# Sheet4_Matrix.net
KiCad netlist of a schematic drawn in Altium Designer
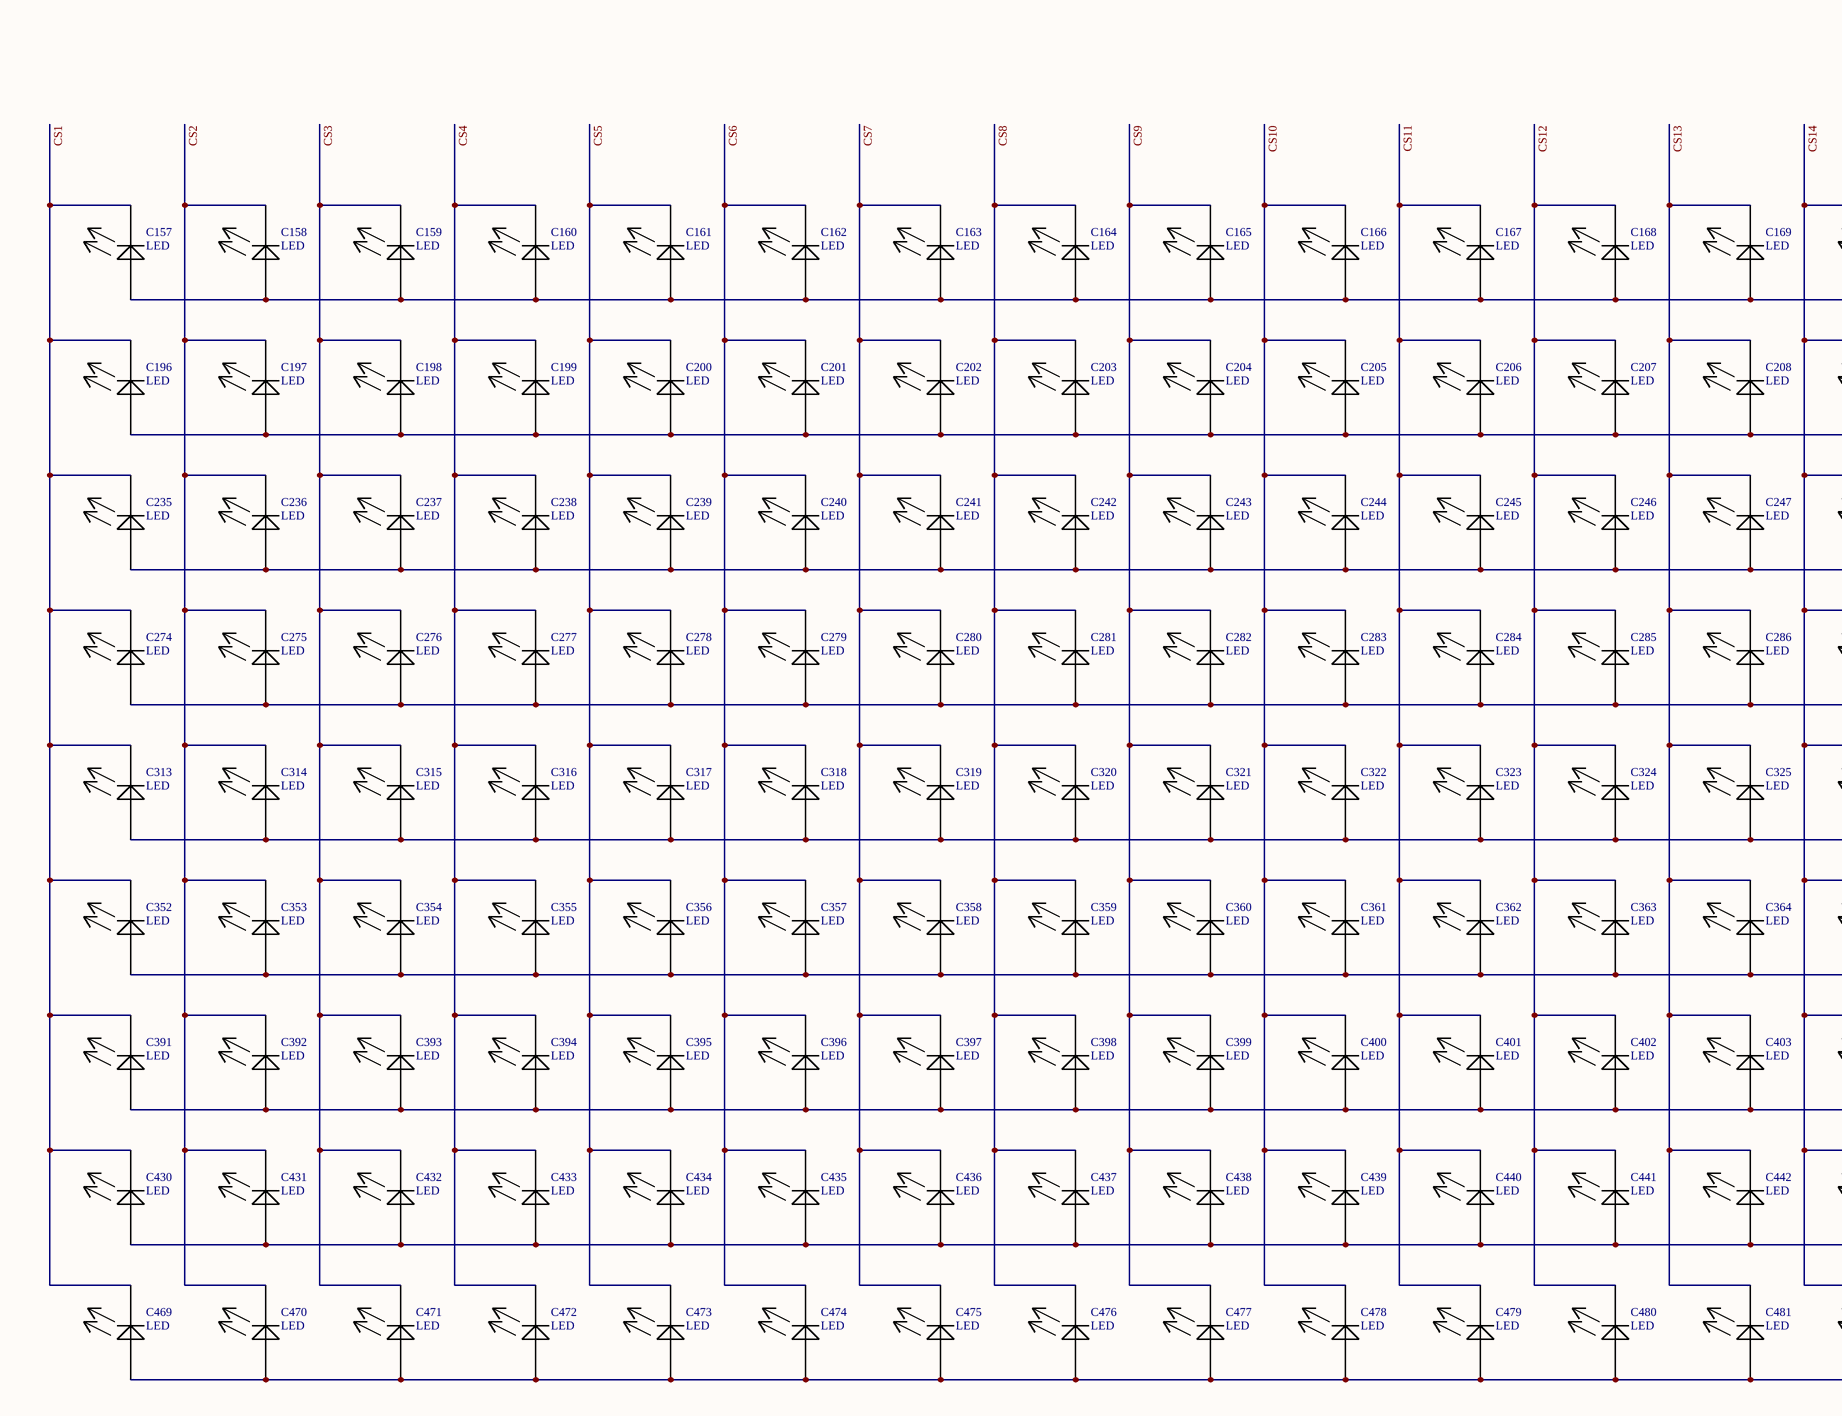
[diagram p0: Sheet4_Matrix.SchDoc, left]
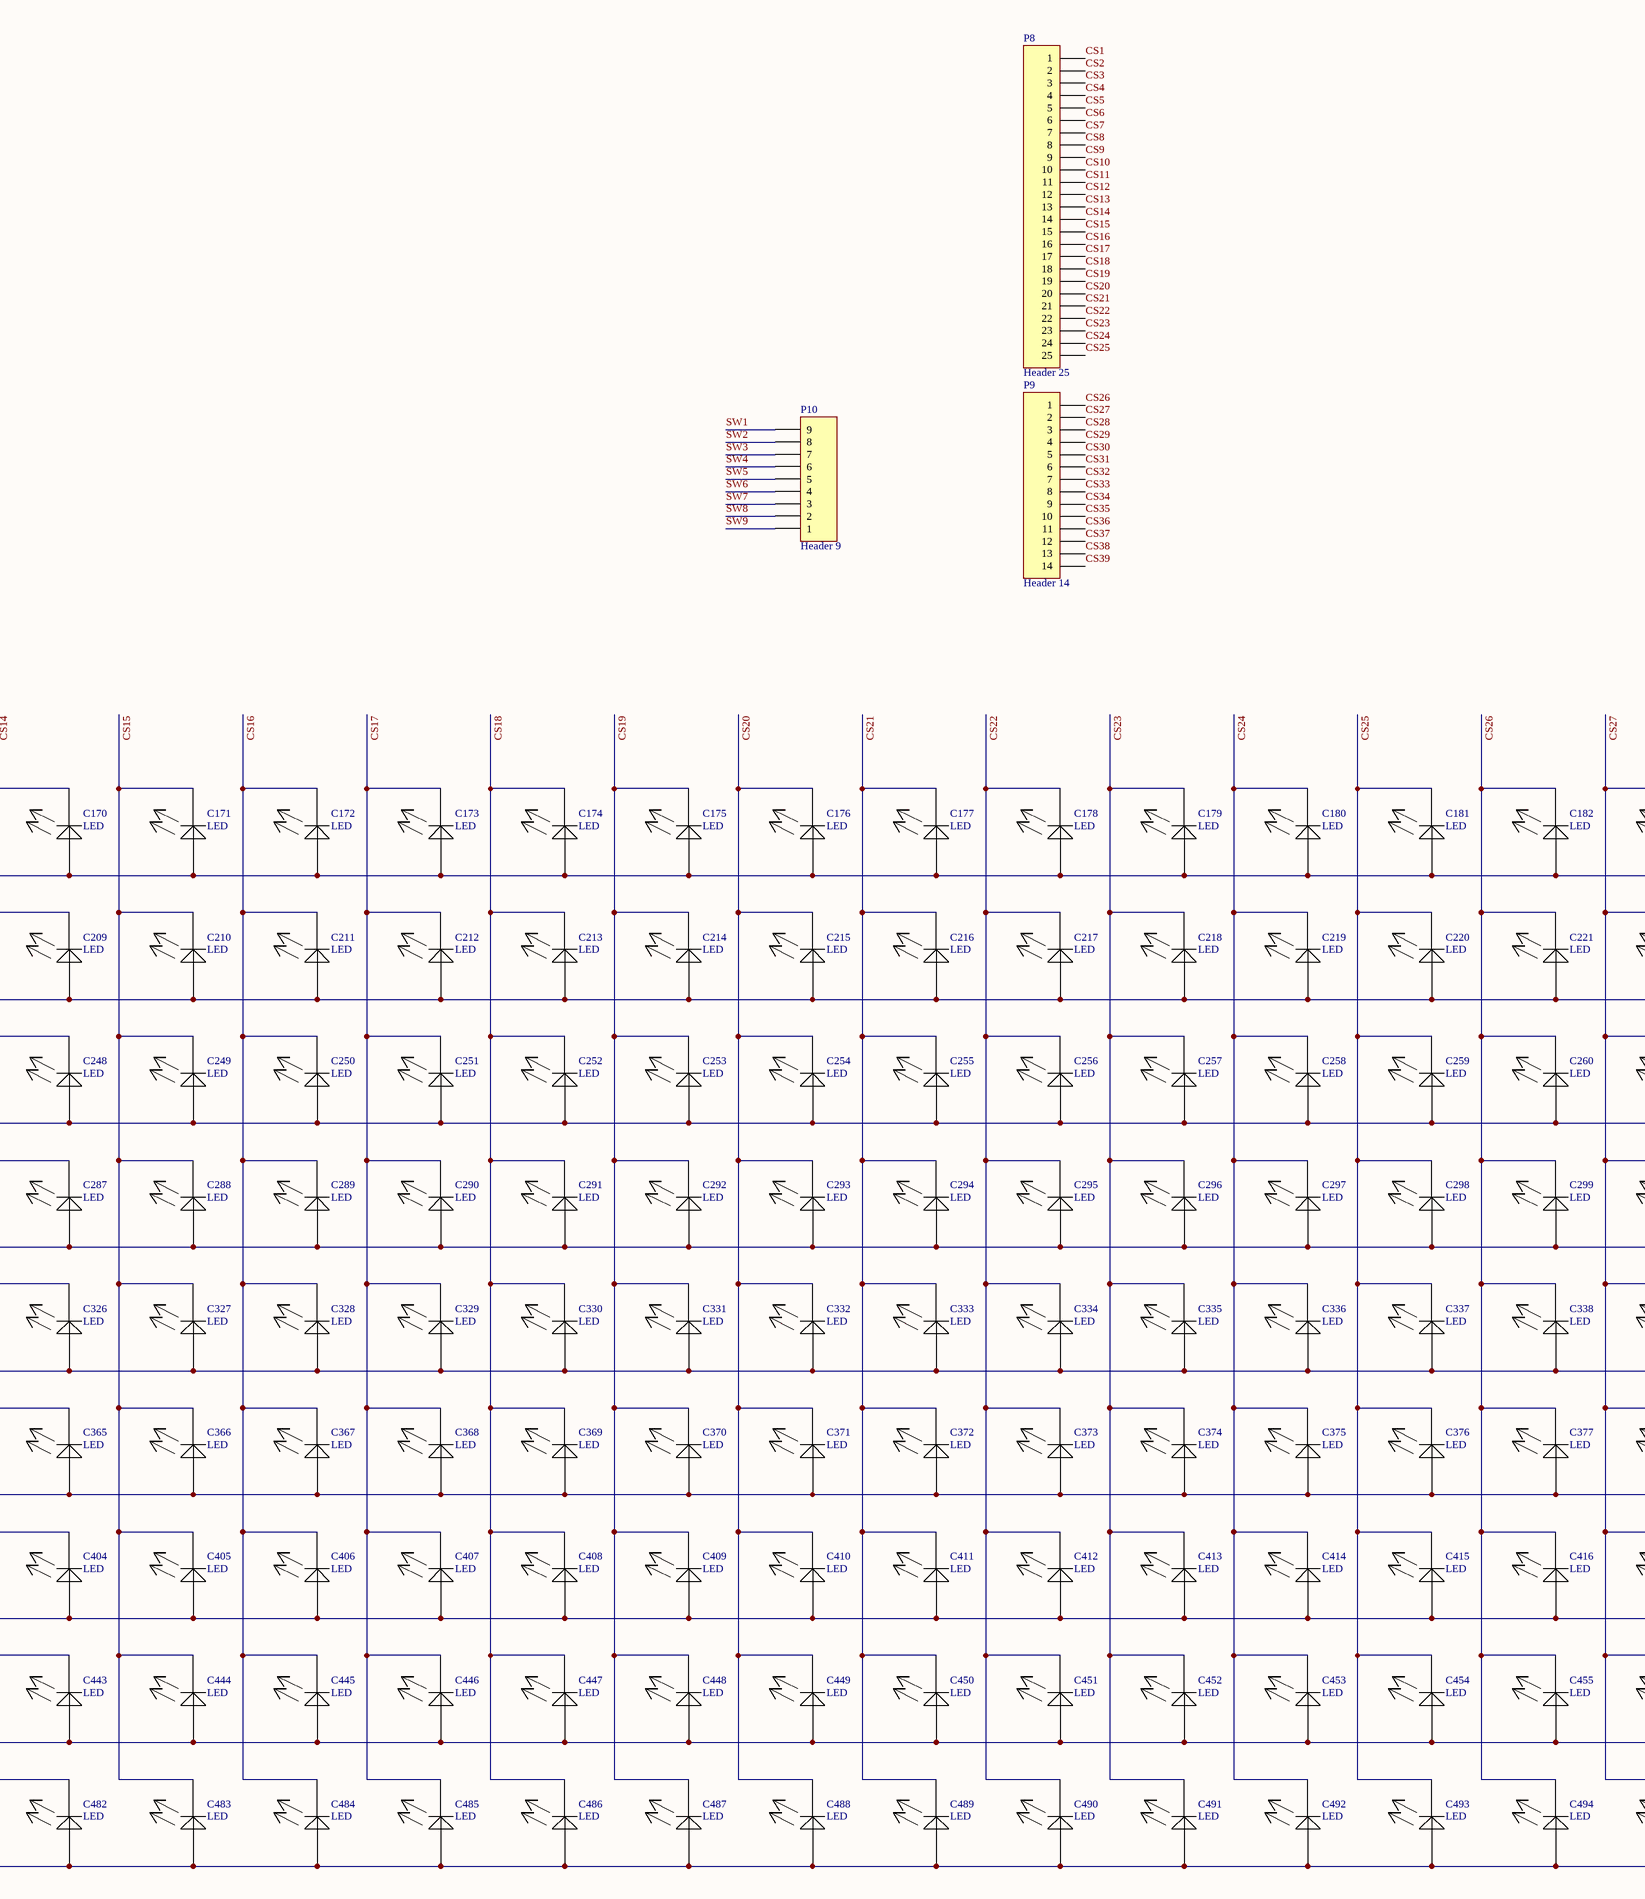
[diagram p1: Sheet4_Matrix.SchDoc, middle]
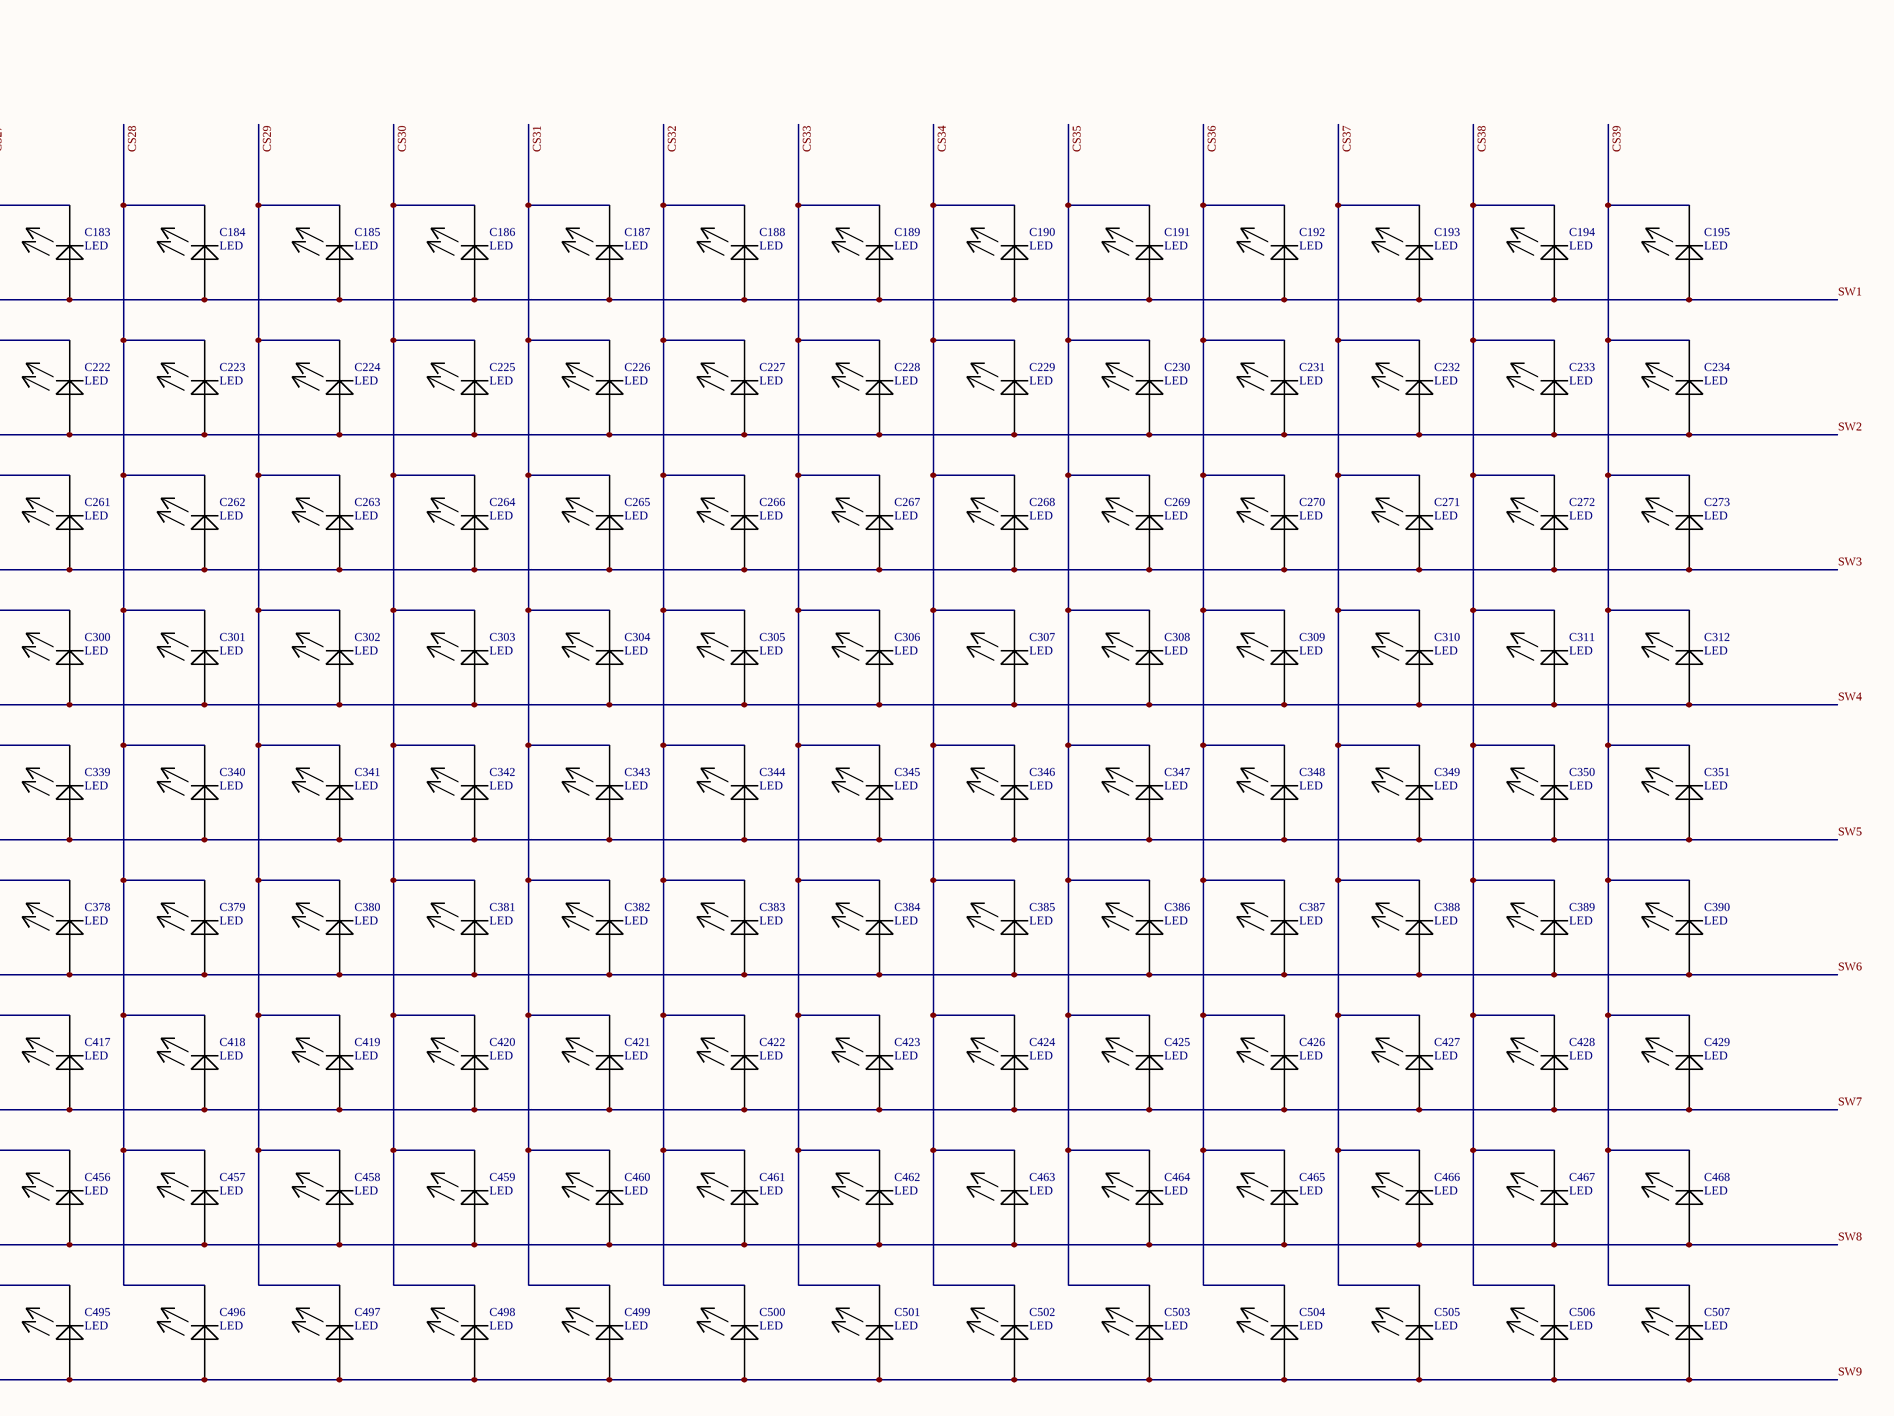
[diagram p2: Sheet4_Matrix.SchDoc, right]

(export (version "E")
  (design (tool "Eeschema 10.0.6"))
  (components
    (comp (ref "C157") (value "LED") (footprint "LED 0603(2)") (libsource (lib "LEDs") (part "LED")))
    (comp (ref "C158") (value "LED") (footprint "LED 0603(2)") (libsource (lib "LEDs") (part "LED")))
    (comp (ref "C159") (value "LED") (footprint "LED 0603(2)") (libsource (lib "LEDs") (part "LED")))
    (comp (ref "C160") (value "LED") (footprint "LED 0603(2)") (libsource (lib "LEDs") (part "LED")))
    (comp (ref "C161") (value "LED") (footprint "LED 0603(2)") (libsource (lib "LEDs") (part "LED")))
    (comp (ref "C162") (value "LED") (footprint "LED 0603(2)") (libsource (lib "LEDs") (part "LED")))
    (comp (ref "C163") (value "LED") (footprint "LED 0603(2)") (libsource (lib "LEDs") (part "LED")))
    (comp (ref "C164") (value "LED") (footprint "LED 0603(2)") (libsource (lib "LEDs") (part "LED")))
    (comp (ref "C165") (value "LED") (footprint "LED 0603(2)") (libsource (lib "LEDs") (part "LED")))
    (comp (ref "C166") (value "LED") (footprint "LED 0603(2)") (libsource (lib "LEDs") (part "LED")))
    (comp (ref "C167") (value "LED") (footprint "LED 0603(2)") (libsource (lib "LEDs") (part "LED")))
    (comp (ref "C168") (value "LED") (footprint "LED 0603(2)") (libsource (lib "LEDs") (part "LED")))
    (comp (ref "C169") (value "LED") (footprint "LED 0603(2)") (libsource (lib "LEDs") (part "LED")))
    (comp (ref "C170") (value "LED") (footprint "LED 0603(2)") (libsource (lib "LEDs") (part "LED")))
    (comp (ref "C171") (value "LED") (footprint "LED 0603(2)") (libsource (lib "LEDs") (part "LED")))
    (comp (ref "C172") (value "LED") (footprint "LED 0603(2)") (libsource (lib "LEDs") (part "LED")))
    (comp (ref "C173") (value "LED") (footprint "LED 0603(2)") (libsource (lib "LEDs") (part "LED")))
    (comp (ref "C174") (value "LED") (footprint "LED 0603(2)") (libsource (lib "LEDs") (part "LED")))
    (comp (ref "C175") (value "LED") (footprint "LED 0603(2)") (libsource (lib "LEDs") (part "LED")))
    (comp (ref "C176") (value "LED") (footprint "LED 0603(2)") (libsource (lib "LEDs") (part "LED")))
    (comp (ref "C177") (value "LED") (footprint "LED 0603(2)") (libsource (lib "LEDs") (part "LED")))
    (comp (ref "C178") (value "LED") (footprint "LED 0603(2)") (libsource (lib "LEDs") (part "LED")))
    (comp (ref "C179") (value "LED") (footprint "LED 0603(2)") (libsource (lib "LEDs") (part "LED")))
    (comp (ref "C180") (value "LED") (footprint "LED 0603(2)") (libsource (lib "LEDs") (part "LED")))
    (comp (ref "C181") (value "LED") (footprint "LED 0603(2)") (libsource (lib "LEDs") (part "LED")))
    (comp (ref "C182") (value "LED") (footprint "LED 0603(2)") (libsource (lib "LEDs") (part "LED")))
    (comp (ref "C183") (value "LED") (footprint "LED 0603(2)") (libsource (lib "LEDs") (part "LED")))
    (comp (ref "C184") (value "LED") (footprint "LED 0603(2)") (libsource (lib "LEDs") (part "LED")))
    (comp (ref "C185") (value "LED") (footprint "LED 0603(2)") (libsource (lib "LEDs") (part "LED")))
    (comp (ref "C186") (value "LED") (footprint "LED 0603(2)") (libsource (lib "LEDs") (part "LED")))
    (comp (ref "C187") (value "LED") (footprint "LED 0603(2)") (libsource (lib "LEDs") (part "LED")))
    (comp (ref "C188") (value "LED") (footprint "LED 0603(2)") (libsource (lib "LEDs") (part "LED")))
    (comp (ref "C189") (value "LED") (footprint "LED 0603(2)") (libsource (lib "LEDs") (part "LED")))
    (comp (ref "C190") (value "LED") (footprint "LED 0603(2)") (libsource (lib "LEDs") (part "LED")))
    (comp (ref "C191") (value "LED") (footprint "LED 0603(2)") (libsource (lib "LEDs") (part "LED")))
    (comp (ref "C192") (value "LED") (footprint "LED 0603(2)") (libsource (lib "LEDs") (part "LED")))
    (comp (ref "C193") (value "LED") (footprint "LED 0603(2)") (libsource (lib "LEDs") (part "LED")))
    (comp (ref "C194") (value "LED") (footprint "LED 0603(2)") (libsource (lib "LEDs") (part "LED")))
    (comp (ref "C195") (value "LED") (footprint "LED 0603(2)") (libsource (lib "LEDs") (part "LED")))
    (comp (ref "C196") (value "LED") (footprint "LED 0603(2)") (libsource (lib "LEDs") (part "LED")))
    (comp (ref "C197") (value "LED") (footprint "LED 0603(2)") (libsource (lib "LEDs") (part "LED")))
    (comp (ref "C198") (value "LED") (footprint "LED 0603(2)") (libsource (lib "LEDs") (part "LED")))
    (comp (ref "C199") (value "LED") (footprint "LED 0603(2)") (libsource (lib "LEDs") (part "LED")))
    (comp (ref "C200") (value "LED") (footprint "LED 0603(2)") (libsource (lib "LEDs") (part "LED")))
    (comp (ref "C201") (value "LED") (footprint "LED 0603(2)") (libsource (lib "LEDs") (part "LED")))
    (comp (ref "C202") (value "LED") (footprint "LED 0603(2)") (libsource (lib "LEDs") (part "LED")))
    (comp (ref "C203") (value "LED") (footprint "LED 0603(2)") (libsource (lib "LEDs") (part "LED")))
    (comp (ref "C204") (value "LED") (footprint "LED 0603(2)") (libsource (lib "LEDs") (part "LED")))
    (comp (ref "C205") (value "LED") (footprint "LED 0603(2)") (libsource (lib "LEDs") (part "LED")))
    (comp (ref "C206") (value "LED") (footprint "LED 0603(2)") (libsource (lib "LEDs") (part "LED")))
    (comp (ref "C207") (value "LED") (footprint "LED 0603(2)") (libsource (lib "LEDs") (part "LED")))
    (comp (ref "C208") (value "LED") (footprint "LED 0603(2)") (libsource (lib "LEDs") (part "LED")))
    (comp (ref "C209") (value "LED") (footprint "LED 0603(2)") (libsource (lib "LEDs") (part "LED")))
    (comp (ref "C210") (value "LED") (footprint "LED 0603(2)") (libsource (lib "LEDs") (part "LED")))
    (comp (ref "C211") (value "LED") (footprint "LED 0603(2)") (libsource (lib "LEDs") (part "LED")))
    (comp (ref "C212") (value "LED") (footprint "LED 0603(2)") (libsource (lib "LEDs") (part "LED")))
    (comp (ref "C213") (value "LED") (footprint "LED 0603(2)") (libsource (lib "LEDs") (part "LED")))
    (comp (ref "C214") (value "LED") (footprint "LED 0603(2)") (libsource (lib "LEDs") (part "LED")))
    (comp (ref "C215") (value "LED") (footprint "LED 0603(2)") (libsource (lib "LEDs") (part "LED")))
    (comp (ref "C216") (value "LED") (footprint "LED 0603(2)") (libsource (lib "LEDs") (part "LED")))
    (comp (ref "C217") (value "LED") (footprint "LED 0603(2)") (libsource (lib "LEDs") (part "LED")))
    (comp (ref "C218") (value "LED") (footprint "LED 0603(2)") (libsource (lib "LEDs") (part "LED")))
    (comp (ref "C219") (value "LED") (footprint "LED 0603(2)") (libsource (lib "LEDs") (part "LED")))
    (comp (ref "C220") (value "LED") (footprint "LED 0603(2)") (libsource (lib "LEDs") (part "LED")))
    (comp (ref "C221") (value "LED") (footprint "LED 0603(2)") (libsource (lib "LEDs") (part "LED")))
    (comp (ref "C222") (value "LED") (footprint "LED 0603(2)") (libsource (lib "LEDs") (part "LED")))
    (comp (ref "C223") (value "LED") (footprint "LED 0603(2)") (libsource (lib "LEDs") (part "LED")))
    (comp (ref "C224") (value "LED") (footprint "LED 0603(2)") (libsource (lib "LEDs") (part "LED")))
    (comp (ref "C225") (value "LED") (footprint "LED 0603(2)") (libsource (lib "LEDs") (part "LED")))
    (comp (ref "C226") (value "LED") (footprint "LED 0603(2)") (libsource (lib "LEDs") (part "LED")))
    (comp (ref "C227") (value "LED") (footprint "LED 0603(2)") (libsource (lib "LEDs") (part "LED")))
    (comp (ref "C228") (value "LED") (footprint "LED 0603(2)") (libsource (lib "LEDs") (part "LED")))
    (comp (ref "C229") (value "LED") (footprint "LED 0603(2)") (libsource (lib "LEDs") (part "LED")))
    (comp (ref "C230") (value "LED") (footprint "LED 0603(2)") (libsource (lib "LEDs") (part "LED")))
    (comp (ref "C231") (value "LED") (footprint "LED 0603(2)") (libsource (lib "LEDs") (part "LED")))
    (comp (ref "C232") (value "LED") (footprint "LED 0603(2)") (libsource (lib "LEDs") (part "LED")))
    (comp (ref "C233") (value "LED") (footprint "LED 0603(2)") (libsource (lib "LEDs") (part "LED")))
    (comp (ref "C234") (value "LED") (footprint "LED 0603(2)") (libsource (lib "LEDs") (part "LED")))
    (comp (ref "C235") (value "LED") (footprint "LED 0603(2)") (libsource (lib "LEDs") (part "LED")))
    (comp (ref "C236") (value "LED") (footprint "LED 0603(2)") (libsource (lib "LEDs") (part "LED")))
    (comp (ref "C237") (value "LED") (footprint "LED 0603(2)") (libsource (lib "LEDs") (part "LED")))
    (comp (ref "C238") (value "LED") (footprint "LED 0603(2)") (libsource (lib "LEDs") (part "LED")))
    (comp (ref "C239") (value "LED") (footprint "LED 0603(2)") (libsource (lib "LEDs") (part "LED")))
    (comp (ref "C240") (value "LED") (footprint "LED 0603(2)") (libsource (lib "LEDs") (part "LED")))
    (comp (ref "C241") (value "LED") (footprint "LED 0603(2)") (libsource (lib "LEDs") (part "LED")))
    (comp (ref "C242") (value "LED") (footprint "LED 0603(2)") (libsource (lib "LEDs") (part "LED")))
    (comp (ref "C243") (value "LED") (footprint "LED 0603(2)") (libsource (lib "LEDs") (part "LED")))
    (comp (ref "C244") (value "LED") (footprint "LED 0603(2)") (libsource (lib "LEDs") (part "LED")))
    (comp (ref "C245") (value "LED") (footprint "LED 0603(2)") (libsource (lib "LEDs") (part "LED")))
    (comp (ref "C246") (value "LED") (footprint "LED 0603(2)") (libsource (lib "LEDs") (part "LED")))
    (comp (ref "C247") (value "LED") (footprint "LED 0603(2)") (libsource (lib "LEDs") (part "LED")))
    (comp (ref "C248") (value "LED") (footprint "LED 0603(2)") (libsource (lib "LEDs") (part "LED")))
    (comp (ref "C249") (value "LED") (footprint "LED 0603(2)") (libsource (lib "LEDs") (part "LED")))
    (comp (ref "C250") (value "LED") (footprint "LED 0603(2)") (libsource (lib "LEDs") (part "LED")))
    (comp (ref "C251") (value "LED") (footprint "LED 0603(2)") (libsource (lib "LEDs") (part "LED")))
    (comp (ref "C252") (value "LED") (footprint "LED 0603(2)") (libsource (lib "LEDs") (part "LED")))
    (comp (ref "C253") (value "LED") (footprint "LED 0603(2)") (libsource (lib "LEDs") (part "LED")))
    (comp (ref "C254") (value "LED") (footprint "LED 0603(2)") (libsource (lib "LEDs") (part "LED")))
    (comp (ref "C255") (value "LED") (footprint "LED 0603(2)") (libsource (lib "LEDs") (part "LED")))
    (comp (ref "C256") (value "LED") (footprint "LED 0603(2)") (libsource (lib "LEDs") (part "LED")))
    (comp (ref "C257") (value "LED") (footprint "LED 0603(2)") (libsource (lib "LEDs") (part "LED")))
    (comp (ref "C258") (value "LED") (footprint "LED 0603(2)") (libsource (lib "LEDs") (part "LED")))
    (comp (ref "C259") (value "LED") (footprint "LED 0603(2)") (libsource (lib "LEDs") (part "LED")))
    (comp (ref "C260") (value "LED") (footprint "LED 0603(2)") (libsource (lib "LEDs") (part "LED")))
    (comp (ref "C261") (value "LED") (footprint "LED 0603(2)") (libsource (lib "LEDs") (part "LED")))
    (comp (ref "C262") (value "LED") (footprint "LED 0603(2)") (libsource (lib "LEDs") (part "LED")))
    (comp (ref "C263") (value "LED") (footprint "LED 0603(2)") (libsource (lib "LEDs") (part "LED")))
    (comp (ref "C264") (value "LED") (footprint "LED 0603(2)") (libsource (lib "LEDs") (part "LED")))
    (comp (ref "C265") (value "LED") (footprint "LED 0603(2)") (libsource (lib "LEDs") (part "LED")))
    (comp (ref "C266") (value "LED") (footprint "LED 0603(2)") (libsource (lib "LEDs") (part "LED")))
    (comp (ref "C267") (value "LED") (footprint "LED 0603(2)") (libsource (lib "LEDs") (part "LED")))
    (comp (ref "C268") (value "LED") (footprint "LED 0603(2)") (libsource (lib "LEDs") (part "LED")))
    (comp (ref "C269") (value "LED") (footprint "LED 0603(2)") (libsource (lib "LEDs") (part "LED")))
    (comp (ref "C270") (value "LED") (footprint "LED 0603(2)") (libsource (lib "LEDs") (part "LED")))
    (comp (ref "C271") (value "LED") (footprint "LED 0603(2)") (libsource (lib "LEDs") (part "LED")))
    (comp (ref "C272") (value "LED") (footprint "LED 0603(2)") (libsource (lib "LEDs") (part "LED")))
    (comp (ref "C273") (value "LED") (footprint "LED 0603(2)") (libsource (lib "LEDs") (part "LED")))
    (comp (ref "C274") (value "LED") (footprint "LED 0603(2)") (libsource (lib "LEDs") (part "LED")))
    (comp (ref "C275") (value "LED") (footprint "LED 0603(2)") (libsource (lib "LEDs") (part "LED")))
    (comp (ref "C276") (value "LED") (footprint "LED 0603(2)") (libsource (lib "LEDs") (part "LED")))
    (comp (ref "C277") (value "LED") (footprint "LED 0603(2)") (libsource (lib "LEDs") (part "LED")))
    (comp (ref "C278") (value "LED") (footprint "LED 0603(2)") (libsource (lib "LEDs") (part "LED")))
    (comp (ref "C279") (value "LED") (footprint "LED 0603(2)") (libsource (lib "LEDs") (part "LED")))
    (comp (ref "C280") (value "LED") (footprint "LED 0603(2)") (libsource (lib "LEDs") (part "LED")))
    (comp (ref "C281") (value "LED") (footprint "LED 0603(2)") (libsource (lib "LEDs") (part "LED")))
    (comp (ref "C282") (value "LED") (footprint "LED 0603(2)") (libsource (lib "LEDs") (part "LED")))
    (comp (ref "C283") (value "LED") (footprint "LED 0603(2)") (libsource (lib "LEDs") (part "LED")))
    (comp (ref "C284") (value "LED") (footprint "LED 0603(2)") (libsource (lib "LEDs") (part "LED")))
    (comp (ref "C285") (value "LED") (footprint "LED 0603(2)") (libsource (lib "LEDs") (part "LED")))
    (comp (ref "C286") (value "LED") (footprint "LED 0603(2)") (libsource (lib "LEDs") (part "LED")))
    (comp (ref "C287") (value "LED") (footprint "LED 0603(2)") (libsource (lib "LEDs") (part "LED")))
    (comp (ref "C288") (value "LED") (footprint "LED 0603(2)") (libsource (lib "LEDs") (part "LED")))
    (comp (ref "C289") (value "LED") (footprint "LED 0603(2)") (libsource (lib "LEDs") (part "LED")))
    (comp (ref "C290") (value "LED") (footprint "LED 0603(2)") (libsource (lib "LEDs") (part "LED")))
    (comp (ref "C291") (value "LED") (footprint "LED 0603(2)") (libsource (lib "LEDs") (part "LED")))
    (comp (ref "C292") (value "LED") (footprint "LED 0603(2)") (libsource (lib "LEDs") (part "LED")))
    (comp (ref "C293") (value "LED") (footprint "LED 0603(2)") (libsource (lib "LEDs") (part "LED")))
    (comp (ref "C294") (value "LED") (footprint "LED 0603(2)") (libsource (lib "LEDs") (part "LED")))
    (comp (ref "C295") (value "LED") (footprint "LED 0603(2)") (libsource (lib "LEDs") (part "LED")))
    (comp (ref "C296") (value "LED") (footprint "LED 0603(2)") (libsource (lib "LEDs") (part "LED")))
    (comp (ref "C297") (value "LED") (footprint "LED 0603(2)") (libsource (lib "LEDs") (part "LED")))
    (comp (ref "C298") (value "LED") (footprint "LED 0603(2)") (libsource (lib "LEDs") (part "LED")))
    (comp (ref "C299") (value "LED") (footprint "LED 0603(2)") (libsource (lib "LEDs") (part "LED")))
    (comp (ref "C300") (value "LED") (footprint "LED 0603(2)") (libsource (lib "LEDs") (part "LED")))
    (comp (ref "C301") (value "LED") (footprint "LED 0603(2)") (libsource (lib "LEDs") (part "LED")))
    (comp (ref "C302") (value "LED") (footprint "LED 0603(2)") (libsource (lib "LEDs") (part "LED")))
    (comp (ref "C303") (value "LED") (footprint "LED 0603(2)") (libsource (lib "LEDs") (part "LED")))
    (comp (ref "C304") (value "LED") (footprint "LED 0603(2)") (libsource (lib "LEDs") (part "LED")))
    (comp (ref "C305") (value "LED") (footprint "LED 0603(2)") (libsource (lib "LEDs") (part "LED")))
    (comp (ref "C306") (value "LED") (footprint "LED 0603(2)") (libsource (lib "LEDs") (part "LED")))
    (comp (ref "C307") (value "LED") (footprint "LED 0603(2)") (libsource (lib "LEDs") (part "LED")))
    (comp (ref "C308") (value "LED") (footprint "LED 0603(2)") (libsource (lib "LEDs") (part "LED")))
    (comp (ref "C309") (value "LED") (footprint "LED 0603(2)") (libsource (lib "LEDs") (part "LED")))
    (comp (ref "C310") (value "LED") (footprint "LED 0603(2)") (libsource (lib "LEDs") (part "LED")))
    (comp (ref "C311") (value "LED") (footprint "LED 0603(2)") (libsource (lib "LEDs") (part "LED")))
    (comp (ref "C312") (value "LED") (footprint "LED 0603(2)") (libsource (lib "LEDs") (part "LED")))
    (comp (ref "C313") (value "LED") (footprint "LED 0603(2)") (libsource (lib "LEDs") (part "LED")))
    (comp (ref "C314") (value "LED") (footprint "LED 0603(2)") (libsource (lib "LEDs") (part "LED")))
    (comp (ref "C315") (value "LED") (footprint "LED 0603(2)") (libsource (lib "LEDs") (part "LED")))
    (comp (ref "C316") (value "LED") (footprint "LED 0603(2)") (libsource (lib "LEDs") (part "LED")))
    (comp (ref "C317") (value "LED") (footprint "LED 0603(2)") (libsource (lib "LEDs") (part "LED")))
    (comp (ref "C318") (value "LED") (footprint "LED 0603(2)") (libsource (lib "LEDs") (part "LED")))
    (comp (ref "C319") (value "LED") (footprint "LED 0603(2)") (libsource (lib "LEDs") (part "LED")))
    (comp (ref "C320") (value "LED") (footprint "LED 0603(2)") (libsource (lib "LEDs") (part "LED")))
    (comp (ref "C321") (value "LED") (footprint "LED 0603(2)") (libsource (lib "LEDs") (part "LED")))
    (comp (ref "C322") (value "LED") (footprint "LED 0603(2)") (libsource (lib "LEDs") (part "LED")))
    (comp (ref "C323") (value "LED") (footprint "LED 0603(2)") (libsource (lib "LEDs") (part "LED")))
    (comp (ref "C324") (value "LED") (footprint "LED 0603(2)") (libsource (lib "LEDs") (part "LED")))
    (comp (ref "C325") (value "LED") (footprint "LED 0603(2)") (libsource (lib "LEDs") (part "LED")))
    (comp (ref "C326") (value "LED") (footprint "LED 0603(2)") (libsource (lib "LEDs") (part "LED")))
    (comp (ref "C327") (value "LED") (footprint "LED 0603(2)") (libsource (lib "LEDs") (part "LED")))
    (comp (ref "C328") (value "LED") (footprint "LED 0603(2)") (libsource (lib "LEDs") (part "LED")))
    (comp (ref "C329") (value "LED") (footprint "LED 0603(2)") (libsource (lib "LEDs") (part "LED")))
    (comp (ref "C330") (value "LED") (footprint "LED 0603(2)") (libsource (lib "LEDs") (part "LED")))
    (comp (ref "C331") (value "LED") (footprint "LED 0603(2)") (libsource (lib "LEDs") (part "LED")))
    (comp (ref "C332") (value "LED") (footprint "LED 0603(2)") (libsource (lib "LEDs") (part "LED")))
    (comp (ref "C333") (value "LED") (footprint "LED 0603(2)") (libsource (lib "LEDs") (part "LED")))
    (comp (ref "C334") (value "LED") (footprint "LED 0603(2)") (libsource (lib "LEDs") (part "LED")))
    (comp (ref "C335") (value "LED") (footprint "LED 0603(2)") (libsource (lib "LEDs") (part "LED")))
    (comp (ref "C336") (value "LED") (footprint "LED 0603(2)") (libsource (lib "LEDs") (part "LED")))
    (comp (ref "C337") (value "LED") (footprint "LED 0603(2)") (libsource (lib "LEDs") (part "LED")))
    (comp (ref "C338") (value "LED") (footprint "LED 0603(2)") (libsource (lib "LEDs") (part "LED")))
    (comp (ref "C339") (value "LED") (footprint "LED 0603(2)") (libsource (lib "LEDs") (part "LED")))
    (comp (ref "C340") (value "LED") (footprint "LED 0603(2)") (libsource (lib "LEDs") (part "LED")))
    (comp (ref "C341") (value "LED") (footprint "LED 0603(2)") (libsource (lib "LEDs") (part "LED")))
    (comp (ref "C342") (value "LED") (footprint "LED 0603(2)") (libsource (lib "LEDs") (part "LED")))
    (comp (ref "C343") (value "LED") (footprint "LED 0603(2)") (libsource (lib "LEDs") (part "LED")))
    (comp (ref "C344") (value "LED") (footprint "LED 0603(2)") (libsource (lib "LEDs") (part "LED")))
    (comp (ref "C345") (value "LED") (footprint "LED 0603(2)") (libsource (lib "LEDs") (part "LED")))
    (comp (ref "C346") (value "LED") (footprint "LED 0603(2)") (libsource (lib "LEDs") (part "LED")))
    (comp (ref "C347") (value "LED") (footprint "LED 0603(2)") (libsource (lib "LEDs") (part "LED")))
    (comp (ref "C348") (value "LED") (footprint "LED 0603(2)") (libsource (lib "LEDs") (part "LED")))
    (comp (ref "C349") (value "LED") (footprint "LED 0603(2)") (libsource (lib "LEDs") (part "LED")))
    (comp (ref "C350") (value "LED") (footprint "LED 0603(2)") (libsource (lib "LEDs") (part "LED")))
    (comp (ref "C351") (value "LED") (footprint "LED 0603(2)") (libsource (lib "LEDs") (part "LED")))
    (comp (ref "C352") (value "LED") (footprint "LED 0603(2)") (libsource (lib "LEDs") (part "LED")))
    (comp (ref "C353") (value "LED") (footprint "LED 0603(2)") (libsource (lib "LEDs") (part "LED")))
    (comp (ref "C354") (value "LED") (footprint "LED 0603(2)") (libsource (lib "LEDs") (part "LED")))
    (comp (ref "C355") (value "LED") (footprint "LED 0603(2)") (libsource (lib "LEDs") (part "LED")))
    (comp (ref "C356") (value "LED") (footprint "LED 0603(2)") (libsource (lib "LEDs") (part "LED")))
    (comp (ref "C357") (value "LED") (footprint "LED 0603(2)") (libsource (lib "LEDs") (part "LED")))
    (comp (ref "C358") (value "LED") (footprint "LED 0603(2)") (libsource (lib "LEDs") (part "LED")))
    (comp (ref "C359") (value "LED") (footprint "LED 0603(2)") (libsource (lib "LEDs") (part "LED")))
    (comp (ref "C360") (value "LED") (footprint "LED 0603(2)") (libsource (lib "LEDs") (part "LED")))
    (comp (ref "C361") (value "LED") (footprint "LED 0603(2)") (libsource (lib "LEDs") (part "LED")))
    (comp (ref "C362") (value "LED") (footprint "LED 0603(2)") (libsource (lib "LEDs") (part "LED")))
    (comp (ref "C363") (value "LED") (footprint "LED 0603(2)") (libsource (lib "LEDs") (part "LED")))
    (comp (ref "C364") (value "LED") (footprint "LED 0603(2)") (libsource (lib "LEDs") (part "LED")))
    (comp (ref "C365") (value "LED") (footprint "LED 0603(2)") (libsource (lib "LEDs") (part "LED")))
    (comp (ref "C366") (value "LED") (footprint "LED 0603(2)") (libsource (lib "LEDs") (part "LED")))
    (comp (ref "C367") (value "LED") (footprint "LED 0603(2)") (libsource (lib "LEDs") (part "LED")))
    (comp (ref "C368") (value "LED") (footprint "LED 0603(2)") (libsource (lib "LEDs") (part "LED")))
    (comp (ref "C369") (value "LED") (footprint "LED 0603(2)") (libsource (lib "LEDs") (part "LED")))
    (comp (ref "C370") (value "LED") (footprint "LED 0603(2)") (libsource (lib "LEDs") (part "LED")))
    (comp (ref "C371") (value "LED") (footprint "LED 0603(2)") (libsource (lib "LEDs") (part "LED")))
    (comp (ref "C372") (value "LED") (footprint "LED 0603(2)") (libsource (lib "LEDs") (part "LED")))
    (comp (ref "C373") (value "LED") (footprint "LED 0603(2)") (libsource (lib "LEDs") (part "LED")))
    (comp (ref "C374") (value "LED") (footprint "LED 0603(2)") (libsource (lib "LEDs") (part "LED")))
    (comp (ref "C375") (value "LED") (footprint "LED 0603(2)") (libsource (lib "LEDs") (part "LED")))
    (comp (ref "C376") (value "LED") (footprint "LED 0603(2)") (libsource (lib "LEDs") (part "LED")))
    (comp (ref "C377") (value "LED") (footprint "LED 0603(2)") (libsource (lib "LEDs") (part "LED")))
    (comp (ref "C378") (value "LED") (footprint "LED 0603(2)") (libsource (lib "LEDs") (part "LED")))
    (comp (ref "C379") (value "LED") (footprint "LED 0603(2)") (libsource (lib "LEDs") (part "LED")))
    (comp (ref "C380") (value "LED") (footprint "LED 0603(2)") (libsource (lib "LEDs") (part "LED")))
    (comp (ref "C381") (value "LED") (footprint "LED 0603(2)") (libsource (lib "LEDs") (part "LED")))
    (comp (ref "C382") (value "LED") (footprint "LED 0603(2)") (libsource (lib "LEDs") (part "LED")))
    (comp (ref "C383") (value "LED") (footprint "LED 0603(2)") (libsource (lib "LEDs") (part "LED")))
    (comp (ref "C384") (value "LED") (footprint "LED 0603(2)") (libsource (lib "LEDs") (part "LED")))
    (comp (ref "C385") (value "LED") (footprint "LED 0603(2)") (libsource (lib "LEDs") (part "LED")))
    (comp (ref "C386") (value "LED") (footprint "LED 0603(2)") (libsource (lib "LEDs") (part "LED")))
    (comp (ref "C387") (value "LED") (footprint "LED 0603(2)") (libsource (lib "LEDs") (part "LED")))
    (comp (ref "C388") (value "LED") (footprint "LED 0603(2)") (libsource (lib "LEDs") (part "LED")))
    (comp (ref "C389") (value "LED") (footprint "LED 0603(2)") (libsource (lib "LEDs") (part "LED")))
    (comp (ref "C390") (value "LED") (footprint "LED 0603(2)") (libsource (lib "LEDs") (part "LED")))
    (comp (ref "C391") (value "LED") (footprint "LED 0603(2)") (libsource (lib "LEDs") (part "LED")))
    (comp (ref "C392") (value "LED") (footprint "LED 0603(2)") (libsource (lib "LEDs") (part "LED")))
    (comp (ref "C393") (value "LED") (footprint "LED 0603(2)") (libsource (lib "LEDs") (part "LED")))
    (comp (ref "C394") (value "LED") (footprint "LED 0603(2)") (libsource (lib "LEDs") (part "LED")))
    (comp (ref "C395") (value "LED") (footprint "LED 0603(2)") (libsource (lib "LEDs") (part "LED")))
    (comp (ref "C396") (value "LED") (footprint "LED 0603(2)") (libsource (lib "LEDs") (part "LED")))
    (comp (ref "C397") (value "LED") (footprint "LED 0603(2)") (libsource (lib "LEDs") (part "LED")))
    (comp (ref "C398") (value "LED") (footprint "LED 0603(2)") (libsource (lib "LEDs") (part "LED")))
    (comp (ref "C399") (value "LED") (footprint "LED 0603(2)") (libsource (lib "LEDs") (part "LED")))
    (comp (ref "C400") (value "LED") (footprint "LED 0603(2)") (libsource (lib "LEDs") (part "LED")))
    (comp (ref "C401") (value "LED") (footprint "LED 0603(2)") (libsource (lib "LEDs") (part "LED")))
    (comp (ref "C402") (value "LED") (footprint "LED 0603(2)") (libsource (lib "LEDs") (part "LED")))
    (comp (ref "C403") (value "LED") (footprint "LED 0603(2)") (libsource (lib "LEDs") (part "LED")))
    (comp (ref "C404") (value "LED") (footprint "LED 0603(2)") (libsource (lib "LEDs") (part "LED")))
    (comp (ref "C405") (value "LED") (footprint "LED 0603(2)") (libsource (lib "LEDs") (part "LED")))
    (comp (ref "C406") (value "LED") (footprint "LED 0603(2)") (libsource (lib "LEDs") (part "LED")))
    (comp (ref "C407") (value "LED") (footprint "LED 0603(2)") (libsource (lib "LEDs") (part "LED")))
    (comp (ref "C408") (value "LED") (footprint "LED 0603(2)") (libsource (lib "LEDs") (part "LED")))
    (comp (ref "C409") (value "LED") (footprint "LED 0603(2)") (libsource (lib "LEDs") (part "LED")))
    (comp (ref "C410") (value "LED") (footprint "LED 0603(2)") (libsource (lib "LEDs") (part "LED")))
    (comp (ref "C411") (value "LED") (footprint "LED 0603(2)") (libsource (lib "LEDs") (part "LED")))
    (comp (ref "C412") (value "LED") (footprint "LED 0603(2)") (libsource (lib "LEDs") (part "LED")))
    (comp (ref "C413") (value "LED") (footprint "LED 0603(2)") (libsource (lib "LEDs") (part "LED")))
    (comp (ref "C414") (value "LED") (footprint "LED 0603(2)") (libsource (lib "LEDs") (part "LED")))
    (comp (ref "C415") (value "LED") (footprint "LED 0603(2)") (libsource (lib "LEDs") (part "LED")))
    (comp (ref "C416") (value "LED") (footprint "LED 0603(2)") (libsource (lib "LEDs") (part "LED")))
    (comp (ref "C417") (value "LED") (footprint "LED 0603(2)") (libsource (lib "LEDs") (part "LED")))
    (comp (ref "C418") (value "LED") (footprint "LED 0603(2)") (libsource (lib "LEDs") (part "LED")))
    (comp (ref "C419") (value "LED") (footprint "LED 0603(2)") (libsource (lib "LEDs") (part "LED")))
    (comp (ref "C420") (value "LED") (footprint "LED 0603(2)") (libsource (lib "LEDs") (part "LED")))
    (comp (ref "C421") (value "LED") (footprint "LED 0603(2)") (libsource (lib "LEDs") (part "LED")))
    (comp (ref "C422") (value "LED") (footprint "LED 0603(2)") (libsource (lib "LEDs") (part "LED")))
    (comp (ref "C423") (value "LED") (footprint "LED 0603(2)") (libsource (lib "LEDs") (part "LED")))
    (comp (ref "C424") (value "LED") (footprint "LED 0603(2)") (libsource (lib "LEDs") (part "LED")))
    (comp (ref "C425") (value "LED") (footprint "LED 0603(2)") (libsource (lib "LEDs") (part "LED")))
    (comp (ref "C426") (value "LED") (footprint "LED 0603(2)") (libsource (lib "LEDs") (part "LED")))
    (comp (ref "C427") (value "LED") (footprint "LED 0603(2)") (libsource (lib "LEDs") (part "LED")))
    (comp (ref "C428") (value "LED") (footprint "LED 0603(2)") (libsource (lib "LEDs") (part "LED")))
    (comp (ref "C429") (value "LED") (footprint "LED 0603(2)") (libsource (lib "LEDs") (part "LED")))
    (comp (ref "C430") (value "LED") (footprint "LED 0603(2)") (libsource (lib "LEDs") (part "LED")))
    (comp (ref "C431") (value "LED") (footprint "LED 0603(2)") (libsource (lib "LEDs") (part "LED")))
    (comp (ref "C432") (value "LED") (footprint "LED 0603(2)") (libsource (lib "LEDs") (part "LED")))
    (comp (ref "C433") (value "LED") (footprint "LED 0603(2)") (libsource (lib "LEDs") (part "LED")))
    (comp (ref "C434") (value "LED") (footprint "LED 0603(2)") (libsource (lib "LEDs") (part "LED")))
    (comp (ref "C435") (value "LED") (footprint "LED 0603(2)") (libsource (lib "LEDs") (part "LED")))
    (comp (ref "C436") (value "LED") (footprint "LED 0603(2)") (libsource (lib "LEDs") (part "LED")))
    (comp (ref "C437") (value "LED") (footprint "LED 0603(2)") (libsource (lib "LEDs") (part "LED")))
    (comp (ref "C438") (value "LED") (footprint "LED 0603(2)") (libsource (lib "LEDs") (part "LED")))
    (comp (ref "C439") (value "LED") (footprint "LED 0603(2)") (libsource (lib "LEDs") (part "LED")))
    (comp (ref "C440") (value "LED") (footprint "LED 0603(2)") (libsource (lib "LEDs") (part "LED")))
    (comp (ref "C441") (value "LED") (footprint "LED 0603(2)") (libsource (lib "LEDs") (part "LED")))
    (comp (ref "C442") (value "LED") (footprint "LED 0603(2)") (libsource (lib "LEDs") (part "LED")))
    (comp (ref "C443") (value "LED") (footprint "LED 0603(2)") (libsource (lib "LEDs") (part "LED")))
    (comp (ref "C444") (value "LED") (footprint "LED 0603(2)") (libsource (lib "LEDs") (part "LED")))
    (comp (ref "C445") (value "LED") (footprint "LED 0603(2)") (libsource (lib "LEDs") (part "LED")))
    (comp (ref "C446") (value "LED") (footprint "LED 0603(2)") (libsource (lib "LEDs") (part "LED")))
    (comp (ref "C447") (value "LED") (footprint "LED 0603(2)") (libsource (lib "LEDs") (part "LED")))
    (comp (ref "C448") (value "LED") (footprint "LED 0603(2)") (libsource (lib "LEDs") (part "LED")))
    (comp (ref "C449") (value "LED") (footprint "LED 0603(2)") (libsource (lib "LEDs") (part "LED")))
    (comp (ref "C450") (value "LED") (footprint "LED 0603(2)") (libsource (lib "LEDs") (part "LED")))
    (comp (ref "C451") (value "LED") (footprint "LED 0603(2)") (libsource (lib "LEDs") (part "LED")))
    (comp (ref "C452") (value "LED") (footprint "LED 0603(2)") (libsource (lib "LEDs") (part "LED")))
    (comp (ref "C453") (value "LED") (footprint "LED 0603(2)") (libsource (lib "LEDs") (part "LED")))
    (comp (ref "C454") (value "LED") (footprint "LED 0603(2)") (libsource (lib "LEDs") (part "LED")))
    (comp (ref "C455") (value "LED") (footprint "LED 0603(2)") (libsource (lib "LEDs") (part "LED")))
    (comp (ref "C456") (value "LED") (footprint "LED 0603(2)") (libsource (lib "LEDs") (part "LED")))
    (comp (ref "C457") (value "LED") (footprint "LED 0603(2)") (libsource (lib "LEDs") (part "LED")))
    (comp (ref "C458") (value "LED") (footprint "LED 0603(2)") (libsource (lib "LEDs") (part "LED")))
    (comp (ref "C459") (value "LED") (footprint "LED 0603(2)") (libsource (lib "LEDs") (part "LED")))
    (comp (ref "C460") (value "LED") (footprint "LED 0603(2)") (libsource (lib "LEDs") (part "LED")))
    (comp (ref "C461") (value "LED") (footprint "LED 0603(2)") (libsource (lib "LEDs") (part "LED")))
    (comp (ref "C462") (value "LED") (footprint "LED 0603(2)") (libsource (lib "LEDs") (part "LED")))
    (comp (ref "C463") (value "LED") (footprint "LED 0603(2)") (libsource (lib "LEDs") (part "LED")))
    (comp (ref "C464") (value "LED") (footprint "LED 0603(2)") (libsource (lib "LEDs") (part "LED")))
    (comp (ref "C465") (value "LED") (footprint "LED 0603(2)") (libsource (lib "LEDs") (part "LED")))
    (comp (ref "C466") (value "LED") (footprint "LED 0603(2)") (libsource (lib "LEDs") (part "LED")))
    (comp (ref "C467") (value "LED") (footprint "LED 0603(2)") (libsource (lib "LEDs") (part "LED")))
    (comp (ref "C468") (value "LED") (footprint "LED 0603(2)") (libsource (lib "LEDs") (part "LED")))
    (comp (ref "C469") (value "LED") (footprint "LED 0603(2)") (libsource (lib "LEDs") (part "LED")))
    (comp (ref "C470") (value "LED") (footprint "LED 0603(2)") (libsource (lib "LEDs") (part "LED")))
    (comp (ref "C471") (value "LED") (footprint "LED 0603(2)") (libsource (lib "LEDs") (part "LED")))
    (comp (ref "C472") (value "LED") (footprint "LED 0603(2)") (libsource (lib "LEDs") (part "LED")))
    (comp (ref "C473") (value "LED") (footprint "LED 0603(2)") (libsource (lib "LEDs") (part "LED")))
    (comp (ref "C474") (value "LED") (footprint "LED 0603(2)") (libsource (lib "LEDs") (part "LED")))
    (comp (ref "C475") (value "LED") (footprint "LED 0603(2)") (libsource (lib "LEDs") (part "LED")))
    (comp (ref "C476") (value "LED") (footprint "LED 0603(2)") (libsource (lib "LEDs") (part "LED")))
    (comp (ref "C477") (value "LED") (footprint "LED 0603(2)") (libsource (lib "LEDs") (part "LED")))
    (comp (ref "C478") (value "LED") (footprint "LED 0603(2)") (libsource (lib "LEDs") (part "LED")))
    (comp (ref "C479") (value "LED") (footprint "LED 0603(2)") (libsource (lib "LEDs") (part "LED")))
    (comp (ref "C480") (value "LED") (footprint "LED 0603(2)") (libsource (lib "LEDs") (part "LED")))
    (comp (ref "C481") (value "LED") (footprint "LED 0603(2)") (libsource (lib "LEDs") (part "LED")))
    (comp (ref "C482") (value "LED") (footprint "LED 0603(2)") (libsource (lib "LEDs") (part "LED")))
    (comp (ref "C483") (value "LED") (footprint "LED 0603(2)") (libsource (lib "LEDs") (part "LED")))
    (comp (ref "C484") (value "LED") (footprint "LED 0603(2)") (libsource (lib "LEDs") (part "LED")))
    (comp (ref "C485") (value "LED") (footprint "LED 0603(2)") (libsource (lib "LEDs") (part "LED")))
    (comp (ref "C486") (value "LED") (footprint "LED 0603(2)") (libsource (lib "LEDs") (part "LED")))
    (comp (ref "C487") (value "LED") (footprint "LED 0603(2)") (libsource (lib "LEDs") (part "LED")))
    (comp (ref "C488") (value "LED") (footprint "LED 0603(2)") (libsource (lib "LEDs") (part "LED")))
    (comp (ref "C489") (value "LED") (footprint "LED 0603(2)") (libsource (lib "LEDs") (part "LED")))
    (comp (ref "C490") (value "LED") (footprint "LED 0603(2)") (libsource (lib "LEDs") (part "LED")))
    (comp (ref "C491") (value "LED") (footprint "LED 0603(2)") (libsource (lib "LEDs") (part "LED")))
    (comp (ref "C492") (value "LED") (footprint "LED 0603(2)") (libsource (lib "LEDs") (part "LED")))
    (comp (ref "C493") (value "LED") (footprint "LED 0603(2)") (libsource (lib "LEDs") (part "LED")))
    (comp (ref "C494") (value "LED") (footprint "LED 0603(2)") (libsource (lib "LEDs") (part "LED")))
    (comp (ref "C495") (value "LED") (footprint "LED 0603(2)") (libsource (lib "LEDs") (part "LED")))
    (comp (ref "C496") (value "LED") (footprint "LED 0603(2)") (libsource (lib "LEDs") (part "LED")))
    (comp (ref "C497") (value "LED") (footprint "LED 0603(2)") (libsource (lib "LEDs") (part "LED")))
    (comp (ref "C498") (value "LED") (footprint "LED 0603(2)") (libsource (lib "LEDs") (part "LED")))
    (comp (ref "C499") (value "LED") (footprint "LED 0603(2)") (libsource (lib "LEDs") (part "LED")))
    (comp (ref "C500") (value "LED") (footprint "LED 0603(2)") (libsource (lib "LEDs") (part "LED")))
    (comp (ref "C501") (value "LED") (footprint "LED 0603(2)") (libsource (lib "LEDs") (part "LED")))
    (comp (ref "C502") (value "LED") (footprint "LED 0603(2)") (libsource (lib "LEDs") (part "LED")))
    (comp (ref "C503") (value "LED") (footprint "LED 0603(2)") (libsource (lib "LEDs") (part "LED")))
    (comp (ref "C504") (value "LED") (footprint "LED 0603(2)") (libsource (lib "LEDs") (part "LED")))
    (comp (ref "C505") (value "LED") (footprint "LED 0603(2)") (libsource (lib "LEDs") (part "LED")))
    (comp (ref "C506") (value "LED") (footprint "LED 0603(2)") (libsource (lib "LEDs") (part "LED")))
    (comp (ref "C507") (value "LED") (footprint "LED 0603(2)") (libsource (lib "LEDs") (part "LED")))
    (comp (ref "P8")
      (value "Header 25")
      (footprint "HDR1X25")
      (description "Header, 25-Pin")
      (fields (field (name "PUBLISHER") "Altium Limited"))
      (libsource (lib "Miscellaneous Connectors") (part "Header 25"))
    )
    (comp (ref "P9")
      (value "Header 14")
      (footprint "HDR1X14")
      (description "Header, 14-Pin")
      (fields (field (name "PUBLISHER") "Altium Limited"))
      (libsource (lib "Miscellaneous Connectors") (part "Header 14"))
    )
    (comp (ref "P10")
      (value "Header 9")
      (footprint "HDR1X9")
      (description "Header, 9-Pin")
      (fields (field (name "PUBLISHER") "Altium Limited"))
      (libsource (lib "Miscellaneous Connectors") (part "Header 9"))
    )
  )
  (nets
    (net (code "1") (name "/CS1") (class "Default")
      (node (ref "C157") (pin "2") (pinfunction "-_2") (pintype "passive"))
      (node (ref "C196") (pin "2") (pinfunction "-_2") (pintype "passive"))
      (node (ref "C235") (pin "2") (pinfunction "-_2") (pintype "passive"))
      (node (ref "C274") (pin "2") (pinfunction "-_2") (pintype "passive"))
      (node (ref "C313") (pin "2") (pinfunction "-_2") (pintype "passive"))
      (node (ref "C352") (pin "2") (pinfunction "-_2") (pintype "passive"))
      (node (ref "C391") (pin "2") (pinfunction "-_2") (pintype "passive"))
      (node (ref "C430") (pin "2") (pinfunction "-_2") (pintype "passive"))
      (node (ref "C469") (pin "2") (pinfunction "-_2") (pintype "passive"))
      (node (ref "P8") (pin "1") (pinfunction "1_1") (pintype "passive"))
    )
    (net (code "2") (name "/CS2") (class "Default")
      (node (ref "C158") (pin "2") (pinfunction "-_2") (pintype "passive"))
      (node (ref "C197") (pin "2") (pinfunction "-_2") (pintype "passive"))
      (node (ref "C236") (pin "2") (pinfunction "-_2") (pintype "passive"))
      (node (ref "C275") (pin "2") (pinfunction "-_2") (pintype "passive"))
      (node (ref "C314") (pin "2") (pinfunction "-_2") (pintype "passive"))
      (node (ref "C353") (pin "2") (pinfunction "-_2") (pintype "passive"))
      (node (ref "C392") (pin "2") (pinfunction "-_2") (pintype "passive"))
      (node (ref "C431") (pin "2") (pinfunction "-_2") (pintype "passive"))
      (node (ref "C470") (pin "2") (pinfunction "-_2") (pintype "passive"))
      (node (ref "P8") (pin "2") (pinfunction "2_2") (pintype "passive"))
    )
    (net (code "3") (name "/CS3") (class "Default")
      (node (ref "C159") (pin "2") (pinfunction "-_2") (pintype "passive"))
      (node (ref "C198") (pin "2") (pinfunction "-_2") (pintype "passive"))
      (node (ref "C237") (pin "2") (pinfunction "-_2") (pintype "passive"))
      (node (ref "C276") (pin "2") (pinfunction "-_2") (pintype "passive"))
      (node (ref "C315") (pin "2") (pinfunction "-_2") (pintype "passive"))
      (node (ref "C354") (pin "2") (pinfunction "-_2") (pintype "passive"))
      (node (ref "C393") (pin "2") (pinfunction "-_2") (pintype "passive"))
      (node (ref "C432") (pin "2") (pinfunction "-_2") (pintype "passive"))
      (node (ref "C471") (pin "2") (pinfunction "-_2") (pintype "passive"))
      (node (ref "P8") (pin "3") (pinfunction "3_3") (pintype "passive"))
    )
    (net (code "4") (name "/CS4") (class "Default")
      (node (ref "C160") (pin "2") (pinfunction "-_2") (pintype "passive"))
      (node (ref "C199") (pin "2") (pinfunction "-_2") (pintype "passive"))
      (node (ref "C238") (pin "2") (pinfunction "-_2") (pintype "passive"))
      (node (ref "C277") (pin "2") (pinfunction "-_2") (pintype "passive"))
      (node (ref "C316") (pin "2") (pinfunction "-_2") (pintype "passive"))
      (node (ref "C355") (pin "2") (pinfunction "-_2") (pintype "passive"))
      (node (ref "C394") (pin "2") (pinfunction "-_2") (pintype "passive"))
      (node (ref "C433") (pin "2") (pinfunction "-_2") (pintype "passive"))
      (node (ref "C472") (pin "2") (pinfunction "-_2") (pintype "passive"))
      (node (ref "P8") (pin "4") (pinfunction "4_4") (pintype "passive"))
    )
    (net (code "5") (name "/CS5") (class "Default")
      (node (ref "C161") (pin "2") (pinfunction "-_2") (pintype "passive"))
      (node (ref "C200") (pin "2") (pinfunction "-_2") (pintype "passive"))
      (node (ref "C239") (pin "2") (pinfunction "-_2") (pintype "passive"))
      (node (ref "C278") (pin "2") (pinfunction "-_2") (pintype "passive"))
      (node (ref "C317") (pin "2") (pinfunction "-_2") (pintype "passive"))
      (node (ref "C356") (pin "2") (pinfunction "-_2") (pintype "passive"))
      (node (ref "C395") (pin "2") (pinfunction "-_2") (pintype "passive"))
      (node (ref "C434") (pin "2") (pinfunction "-_2") (pintype "passive"))
      (node (ref "C473") (pin "2") (pinfunction "-_2") (pintype "passive"))
      (node (ref "P8") (pin "5") (pinfunction "5_5") (pintype "passive"))
    )
    (net (code "6") (name "/CS6") (class "Default")
      (node (ref "C162") (pin "2") (pinfunction "-_2") (pintype "passive"))
      (node (ref "C201") (pin "2") (pinfunction "-_2") (pintype "passive"))
      (node (ref "C240") (pin "2") (pinfunction "-_2") (pintype "passive"))
      (node (ref "C279") (pin "2") (pinfunction "-_2") (pintype "passive"))
      (node (ref "C318") (pin "2") (pinfunction "-_2") (pintype "passive"))
      (node (ref "C357") (pin "2") (pinfunction "-_2") (pintype "passive"))
      (node (ref "C396") (pin "2") (pinfunction "-_2") (pintype "passive"))
      (node (ref "C435") (pin "2") (pinfunction "-_2") (pintype "passive"))
      (node (ref "C474") (pin "2") (pinfunction "-_2") (pintype "passive"))
      (node (ref "P8") (pin "6") (pinfunction "6_6") (pintype "passive"))
    )
    (net (code "7") (name "/CS7") (class "Default")
      (node (ref "C163") (pin "2") (pinfunction "-_2") (pintype "passive"))
      (node (ref "C202") (pin "2") (pinfunction "-_2") (pintype "passive"))
      (node (ref "C241") (pin "2") (pinfunction "-_2") (pintype "passive"))
      (node (ref "C280") (pin "2") (pinfunction "-_2") (pintype "passive"))
      (node (ref "C319") (pin "2") (pinfunction "-_2") (pintype "passive"))
      (node (ref "C358") (pin "2") (pinfunction "-_2") (pintype "passive"))
      (node (ref "C397") (pin "2") (pinfunction "-_2") (pintype "passive"))
      (node (ref "C436") (pin "2") (pinfunction "-_2") (pintype "passive"))
      (node (ref "C475") (pin "2") (pinfunction "-_2") (pintype "passive"))
      (node (ref "P8") (pin "7") (pinfunction "7_7") (pintype "passive"))
    )
    (net (code "8") (name "/CS8") (class "Default")
      (node (ref "C164") (pin "2") (pinfunction "-_2") (pintype "passive"))
      (node (ref "C203") (pin "2") (pinfunction "-_2") (pintype "passive"))
      (node (ref "C242") (pin "2") (pinfunction "-_2") (pintype "passive"))
      (node (ref "C281") (pin "2") (pinfunction "-_2") (pintype "passive"))
      (node (ref "C320") (pin "2") (pinfunction "-_2") (pintype "passive"))
      (node (ref "C359") (pin "2") (pinfunction "-_2") (pintype "passive"))
      (node (ref "C398") (pin "2") (pinfunction "-_2") (pintype "passive"))
      (node (ref "C437") (pin "2") (pinfunction "-_2") (pintype "passive"))
      (node (ref "C476") (pin "2") (pinfunction "-_2") (pintype "passive"))
      (node (ref "P8") (pin "8") (pinfunction "8_8") (pintype "passive"))
    )
    (net (code "9") (name "/CS9") (class "Default")
      (node (ref "C165") (pin "2") (pinfunction "-_2") (pintype "passive"))
      (node (ref "C204") (pin "2") (pinfunction "-_2") (pintype "passive"))
      (node (ref "C243") (pin "2") (pinfunction "-_2") (pintype "passive"))
      (node (ref "C282") (pin "2") (pinfunction "-_2") (pintype "passive"))
      (node (ref "C321") (pin "2") (pinfunction "-_2") (pintype "passive"))
      (node (ref "C360") (pin "2") (pinfunction "-_2") (pintype "passive"))
      (node (ref "C399") (pin "2") (pinfunction "-_2") (pintype "passive"))
      (node (ref "C438") (pin "2") (pinfunction "-_2") (pintype "passive"))
      (node (ref "C477") (pin "2") (pinfunction "-_2") (pintype "passive"))
      (node (ref "P8") (pin "9") (pinfunction "9_9") (pintype "passive"))
    )
    (net (code "10") (name "/CS10") (class "Default")
      (node (ref "C166") (pin "2") (pinfunction "-_2") (pintype "passive"))
      (node (ref "C205") (pin "2") (pinfunction "-_2") (pintype "passive"))
      (node (ref "C244") (pin "2") (pinfunction "-_2") (pintype "passive"))
      (node (ref "C283") (pin "2") (pinfunction "-_2") (pintype "passive"))
      (node (ref "C322") (pin "2") (pinfunction "-_2") (pintype "passive"))
      (node (ref "C361") (pin "2") (pinfunction "-_2") (pintype "passive"))
      (node (ref "C400") (pin "2") (pinfunction "-_2") (pintype "passive"))
      (node (ref "C439") (pin "2") (pinfunction "-_2") (pintype "passive"))
      (node (ref "C478") (pin "2") (pinfunction "-_2") (pintype "passive"))
      (node (ref "P8") (pin "10") (pinfunction "10_10") (pintype "passive"))
    )
    (net (code "11") (name "/CS11") (class "Default")
      (node (ref "C167") (pin "2") (pinfunction "-_2") (pintype "passive"))
      (node (ref "C206") (pin "2") (pinfunction "-_2") (pintype "passive"))
      (node (ref "C245") (pin "2") (pinfunction "-_2") (pintype "passive"))
      (node (ref "C284") (pin "2") (pinfunction "-_2") (pintype "passive"))
      (node (ref "C323") (pin "2") (pinfunction "-_2") (pintype "passive"))
      (node (ref "C362") (pin "2") (pinfunction "-_2") (pintype "passive"))
      (node (ref "C401") (pin "2") (pinfunction "-_2") (pintype "passive"))
      (node (ref "C440") (pin "2") (pinfunction "-_2") (pintype "passive"))
      (node (ref "C479") (pin "2") (pinfunction "-_2") (pintype "passive"))
      (node (ref "P8") (pin "11") (pinfunction "11_11") (pintype "passive"))
    )
    (net (code "12") (name "/CS12") (class "Default")
      (node (ref "C168") (pin "2") (pinfunction "-_2") (pintype "passive"))
      (node (ref "C207") (pin "2") (pinfunction "-_2") (pintype "passive"))
      (node (ref "C246") (pin "2") (pinfunction "-_2") (pintype "passive"))
      (node (ref "C285") (pin "2") (pinfunction "-_2") (pintype "passive"))
      (node (ref "C324") (pin "2") (pinfunction "-_2") (pintype "passive"))
      (node (ref "C363") (pin "2") (pinfunction "-_2") (pintype "passive"))
      (node (ref "C402") (pin "2") (pinfunction "-_2") (pintype "passive"))
      (node (ref "C441") (pin "2") (pinfunction "-_2") (pintype "passive"))
      (node (ref "C480") (pin "2") (pinfunction "-_2") (pintype "passive"))
      (node (ref "P8") (pin "12") (pinfunction "12_12") (pintype "passive"))
    )
    (net (code "13") (name "/CS13") (class "Default")
      (node (ref "C169") (pin "2") (pinfunction "-_2") (pintype "passive"))
      (node (ref "C208") (pin "2") (pinfunction "-_2") (pintype "passive"))
      (node (ref "C247") (pin "2") (pinfunction "-_2") (pintype "passive"))
      (node (ref "C286") (pin "2") (pinfunction "-_2") (pintype "passive"))
      (node (ref "C325") (pin "2") (pinfunction "-_2") (pintype "passive"))
      (node (ref "C364") (pin "2") (pinfunction "-_2") (pintype "passive"))
      (node (ref "C403") (pin "2") (pinfunction "-_2") (pintype "passive"))
      (node (ref "C442") (pin "2") (pinfunction "-_2") (pintype "passive"))
      (node (ref "C481") (pin "2") (pinfunction "-_2") (pintype "passive"))
      (node (ref "P8") (pin "13") (pinfunction "13_13") (pintype "passive"))
    )
    (net (code "14") (name "/CS14") (class "Default")
      (node (ref "C170") (pin "2") (pinfunction "-_2") (pintype "passive"))
      (node (ref "C209") (pin "2") (pinfunction "-_2") (pintype "passive"))
      (node (ref "C248") (pin "2") (pinfunction "-_2") (pintype "passive"))
      (node (ref "C287") (pin "2") (pinfunction "-_2") (pintype "passive"))
      (node (ref "C326") (pin "2") (pinfunction "-_2") (pintype "passive"))
      (node (ref "C365") (pin "2") (pinfunction "-_2") (pintype "passive"))
      (node (ref "C404") (pin "2") (pinfunction "-_2") (pintype "passive"))
      (node (ref "C443") (pin "2") (pinfunction "-_2") (pintype "passive"))
      (node (ref "C482") (pin "2") (pinfunction "-_2") (pintype "passive"))
      (node (ref "P8") (pin "14") (pinfunction "14_14") (pintype "passive"))
    )
    (net (code "15") (name "/CS15") (class "Default")
      (node (ref "C171") (pin "2") (pinfunction "-_2") (pintype "passive"))
      (node (ref "C210") (pin "2") (pinfunction "-_2") (pintype "passive"))
      (node (ref "C249") (pin "2") (pinfunction "-_2") (pintype "passive"))
      (node (ref "C288") (pin "2") (pinfunction "-_2") (pintype "passive"))
      (node (ref "C327") (pin "2") (pinfunction "-_2") (pintype "passive"))
      (node (ref "C366") (pin "2") (pinfunction "-_2") (pintype "passive"))
      (node (ref "C405") (pin "2") (pinfunction "-_2") (pintype "passive"))
      (node (ref "C444") (pin "2") (pinfunction "-_2") (pintype "passive"))
      (node (ref "C483") (pin "2") (pinfunction "-_2") (pintype "passive"))
      (node (ref "P8") (pin "15") (pinfunction "15_15") (pintype "passive"))
    )
    (net (code "16") (name "/CS16") (class "Default")
      (node (ref "C172") (pin "2") (pinfunction "-_2") (pintype "passive"))
      (node (ref "C211") (pin "2") (pinfunction "-_2") (pintype "passive"))
      (node (ref "C250") (pin "2") (pinfunction "-_2") (pintype "passive"))
      (node (ref "C289") (pin "2") (pinfunction "-_2") (pintype "passive"))
      (node (ref "C328") (pin "2") (pinfunction "-_2") (pintype "passive"))
      (node (ref "C367") (pin "2") (pinfunction "-_2") (pintype "passive"))
      (node (ref "C406") (pin "2") (pinfunction "-_2") (pintype "passive"))
      (node (ref "C445") (pin "2") (pinfunction "-_2") (pintype "passive"))
      (node (ref "C484") (pin "2") (pinfunction "-_2") (pintype "passive"))
      (node (ref "P8") (pin "16") (pinfunction "16_16") (pintype "passive"))
    )
    (net (code "17") (name "/CS17") (class "Default")
      (node (ref "C173") (pin "2") (pinfunction "-_2") (pintype "passive"))
      (node (ref "C212") (pin "2") (pinfunction "-_2") (pintype "passive"))
      (node (ref "C251") (pin "2") (pinfunction "-_2") (pintype "passive"))
      (node (ref "C290") (pin "2") (pinfunction "-_2") (pintype "passive"))
      (node (ref "C329") (pin "2") (pinfunction "-_2") (pintype "passive"))
      (node (ref "C368") (pin "2") (pinfunction "-_2") (pintype "passive"))
      (node (ref "C407") (pin "2") (pinfunction "-_2") (pintype "passive"))
      (node (ref "C446") (pin "2") (pinfunction "-_2") (pintype "passive"))
      (node (ref "C485") (pin "2") (pinfunction "-_2") (pintype "passive"))
      (node (ref "P8") (pin "17") (pinfunction "17_17") (pintype "passive"))
    )
    (net (code "18") (name "/CS18") (class "Default")
      (node (ref "C174") (pin "2") (pinfunction "-_2") (pintype "passive"))
      (node (ref "C213") (pin "2") (pinfunction "-_2") (pintype "passive"))
      (node (ref "C252") (pin "2") (pinfunction "-_2") (pintype "passive"))
      (node (ref "C291") (pin "2") (pinfunction "-_2") (pintype "passive"))
      (node (ref "C330") (pin "2") (pinfunction "-_2") (pintype "passive"))
      (node (ref "C369") (pin "2") (pinfunction "-_2") (pintype "passive"))
      (node (ref "C408") (pin "2") (pinfunction "-_2") (pintype "passive"))
      (node (ref "C447") (pin "2") (pinfunction "-_2") (pintype "passive"))
      (node (ref "C486") (pin "2") (pinfunction "-_2") (pintype "passive"))
      (node (ref "P8") (pin "18") (pinfunction "18_18") (pintype "passive"))
    )
    (net (code "19") (name "/CS19") (class "Default")
      (node (ref "C175") (pin "2") (pinfunction "-_2") (pintype "passive"))
      (node (ref "C214") (pin "2") (pinfunction "-_2") (pintype "passive"))
      (node (ref "C253") (pin "2") (pinfunction "-_2") (pintype "passive"))
      (node (ref "C292") (pin "2") (pinfunction "-_2") (pintype "passive"))
      (node (ref "C331") (pin "2") (pinfunction "-_2") (pintype "passive"))
      (node (ref "C370") (pin "2") (pinfunction "-_2") (pintype "passive"))
      (node (ref "C409") (pin "2") (pinfunction "-_2") (pintype "passive"))
      (node (ref "C448") (pin "2") (pinfunction "-_2") (pintype "passive"))
      (node (ref "C487") (pin "2") (pinfunction "-_2") (pintype "passive"))
      (node (ref "P8") (pin "19") (pinfunction "19_19") (pintype "passive"))
    )
    (net (code "20") (name "/CS20") (class "Default")
      (node (ref "C176") (pin "2") (pinfunction "-_2") (pintype "passive"))
      (node (ref "C215") (pin "2") (pinfunction "-_2") (pintype "passive"))
      (node (ref "C254") (pin "2") (pinfunction "-_2") (pintype "passive"))
      (node (ref "C293") (pin "2") (pinfunction "-_2") (pintype "passive"))
      (node (ref "C332") (pin "2") (pinfunction "-_2") (pintype "passive"))
      (node (ref "C371") (pin "2") (pinfunction "-_2") (pintype "passive"))
      (node (ref "C410") (pin "2") (pinfunction "-_2") (pintype "passive"))
      (node (ref "C449") (pin "2") (pinfunction "-_2") (pintype "passive"))
      (node (ref "C488") (pin "2") (pinfunction "-_2") (pintype "passive"))
      (node (ref "P8") (pin "20") (pinfunction "20_20") (pintype "passive"))
    )
    (net (code "21") (name "/CS21") (class "Default")
      (node (ref "C177") (pin "2") (pinfunction "-_2") (pintype "passive"))
      (node (ref "C216") (pin "2") (pinfunction "-_2") (pintype "passive"))
      (node (ref "C255") (pin "2") (pinfunction "-_2") (pintype "passive"))
      (node (ref "C294") (pin "2") (pinfunction "-_2") (pintype "passive"))
      (node (ref "C333") (pin "2") (pinfunction "-_2") (pintype "passive"))
      (node (ref "C372") (pin "2") (pinfunction "-_2") (pintype "passive"))
      (node (ref "C411") (pin "2") (pinfunction "-_2") (pintype "passive"))
      (node (ref "C450") (pin "2") (pinfunction "-_2") (pintype "passive"))
      (node (ref "C489") (pin "2") (pinfunction "-_2") (pintype "passive"))
      (node (ref "P8") (pin "21") (pinfunction "21_21") (pintype "passive"))
    )
    (net (code "22") (name "/CS22") (class "Default")
      (node (ref "C178") (pin "2") (pinfunction "-_2") (pintype "passive"))
      (node (ref "C217") (pin "2") (pinfunction "-_2") (pintype "passive"))
      (node (ref "C256") (pin "2") (pinfunction "-_2") (pintype "passive"))
      (node (ref "C295") (pin "2") (pinfunction "-_2") (pintype "passive"))
      (node (ref "C334") (pin "2") (pinfunction "-_2") (pintype "passive"))
      (node (ref "C373") (pin "2") (pinfunction "-_2") (pintype "passive"))
      (node (ref "C412") (pin "2") (pinfunction "-_2") (pintype "passive"))
      (node (ref "C451") (pin "2") (pinfunction "-_2") (pintype "passive"))
      (node (ref "C490") (pin "2") (pinfunction "-_2") (pintype "passive"))
      (node (ref "P8") (pin "22") (pinfunction "22_22") (pintype "passive"))
    )
    (net (code "23") (name "/CS23") (class "Default")
      (node (ref "C179") (pin "2") (pinfunction "-_2") (pintype "passive"))
      (node (ref "C218") (pin "2") (pinfunction "-_2") (pintype "passive"))
      (node (ref "C257") (pin "2") (pinfunction "-_2") (pintype "passive"))
      (node (ref "C296") (pin "2") (pinfunction "-_2") (pintype "passive"))
      (node (ref "C335") (pin "2") (pinfunction "-_2") (pintype "passive"))
      (node (ref "C374") (pin "2") (pinfunction "-_2") (pintype "passive"))
      (node (ref "C413") (pin "2") (pinfunction "-_2") (pintype "passive"))
      (node (ref "C452") (pin "2") (pinfunction "-_2") (pintype "passive"))
      (node (ref "C491") (pin "2") (pinfunction "-_2") (pintype "passive"))
      (node (ref "P8") (pin "23") (pinfunction "23_23") (pintype "passive"))
    )
    (net (code "24") (name "/CS24") (class "Default")
      (node (ref "C180") (pin "2") (pinfunction "-_2") (pintype "passive"))
      (node (ref "C219") (pin "2") (pinfunction "-_2") (pintype "passive"))
      (node (ref "C258") (pin "2") (pinfunction "-_2") (pintype "passive"))
      (node (ref "C297") (pin "2") (pinfunction "-_2") (pintype "passive"))
      (node (ref "C336") (pin "2") (pinfunction "-_2") (pintype "passive"))
      (node (ref "C375") (pin "2") (pinfunction "-_2") (pintype "passive"))
      (node (ref "C414") (pin "2") (pinfunction "-_2") (pintype "passive"))
      (node (ref "C453") (pin "2") (pinfunction "-_2") (pintype "passive"))
      (node (ref "C492") (pin "2") (pinfunction "-_2") (pintype "passive"))
      (node (ref "P8") (pin "24") (pinfunction "24_24") (pintype "passive"))
    )
    (net (code "25") (name "/CS25") (class "Default")
      (node (ref "C181") (pin "2") (pinfunction "-_2") (pintype "passive"))
      (node (ref "C220") (pin "2") (pinfunction "-_2") (pintype "passive"))
      (node (ref "C259") (pin "2") (pinfunction "-_2") (pintype "passive"))
      (node (ref "C298") (pin "2") (pinfunction "-_2") (pintype "passive"))
      (node (ref "C337") (pin "2") (pinfunction "-_2") (pintype "passive"))
      (node (ref "C376") (pin "2") (pinfunction "-_2") (pintype "passive"))
      (node (ref "C415") (pin "2") (pinfunction "-_2") (pintype "passive"))
      (node (ref "C454") (pin "2") (pinfunction "-_2") (pintype "passive"))
      (node (ref "C493") (pin "2") (pinfunction "-_2") (pintype "passive"))
      (node (ref "P8") (pin "25") (pinfunction "25_25") (pintype "passive"))
    )
    (net (code "26") (name "/CS26") (class "Default")
      (node (ref "C182") (pin "2") (pinfunction "-_2") (pintype "passive"))
      (node (ref "C221") (pin "2") (pinfunction "-_2") (pintype "passive"))
      (node (ref "C260") (pin "2") (pinfunction "-_2") (pintype "passive"))
      (node (ref "C299") (pin "2") (pinfunction "-_2") (pintype "passive"))
      (node (ref "C338") (pin "2") (pinfunction "-_2") (pintype "passive"))
      (node (ref "C377") (pin "2") (pinfunction "-_2") (pintype "passive"))
      (node (ref "C416") (pin "2") (pinfunction "-_2") (pintype "passive"))
      (node (ref "C455") (pin "2") (pinfunction "-_2") (pintype "passive"))
      (node (ref "C494") (pin "2") (pinfunction "-_2") (pintype "passive"))
      (node (ref "P9") (pin "1") (pinfunction "1_1") (pintype "passive"))
    )
    (net (code "27") (name "/CS27") (class "Default")
      (node (ref "C183") (pin "2") (pinfunction "-_2") (pintype "passive"))
      (node (ref "C222") (pin "2") (pinfunction "-_2") (pintype "passive"))
      (node (ref "C261") (pin "2") (pinfunction "-_2") (pintype "passive"))
      (node (ref "C300") (pin "2") (pinfunction "-_2") (pintype "passive"))
      (node (ref "C339") (pin "2") (pinfunction "-_2") (pintype "passive"))
      (node (ref "C378") (pin "2") (pinfunction "-_2") (pintype "passive"))
      (node (ref "C417") (pin "2") (pinfunction "-_2") (pintype "passive"))
      (node (ref "C456") (pin "2") (pinfunction "-_2") (pintype "passive"))
      (node (ref "C495") (pin "2") (pinfunction "-_2") (pintype "passive"))
      (node (ref "P9") (pin "2") (pinfunction "2_2") (pintype "passive"))
    )
    (net (code "28") (name "/CS28") (class "Default")
      (node (ref "C184") (pin "2") (pinfunction "-_2") (pintype "passive"))
      (node (ref "C223") (pin "2") (pinfunction "-_2") (pintype "passive"))
      (node (ref "C262") (pin "2") (pinfunction "-_2") (pintype "passive"))
      (node (ref "C301") (pin "2") (pinfunction "-_2") (pintype "passive"))
      (node (ref "C340") (pin "2") (pinfunction "-_2") (pintype "passive"))
      (node (ref "C379") (pin "2") (pinfunction "-_2") (pintype "passive"))
      (node (ref "C418") (pin "2") (pinfunction "-_2") (pintype "passive"))
      (node (ref "C457") (pin "2") (pinfunction "-_2") (pintype "passive"))
      (node (ref "C496") (pin "2") (pinfunction "-_2") (pintype "passive"))
      (node (ref "P9") (pin "3") (pinfunction "3_3") (pintype "passive"))
    )
    (net (code "29") (name "/CS29") (class "Default")
      (node (ref "C185") (pin "2") (pinfunction "-_2") (pintype "passive"))
      (node (ref "C224") (pin "2") (pinfunction "-_2") (pintype "passive"))
      (node (ref "C263") (pin "2") (pinfunction "-_2") (pintype "passive"))
      (node (ref "C302") (pin "2") (pinfunction "-_2") (pintype "passive"))
      (node (ref "C341") (pin "2") (pinfunction "-_2") (pintype "passive"))
      (node (ref "C380") (pin "2") (pinfunction "-_2") (pintype "passive"))
      (node (ref "C419") (pin "2") (pinfunction "-_2") (pintype "passive"))
      (node (ref "C458") (pin "2") (pinfunction "-_2") (pintype "passive"))
      (node (ref "C497") (pin "2") (pinfunction "-_2") (pintype "passive"))
      (node (ref "P9") (pin "4") (pinfunction "4_4") (pintype "passive"))
    )
    (net (code "30") (name "/CS30") (class "Default")
      (node (ref "C186") (pin "2") (pinfunction "-_2") (pintype "passive"))
      (node (ref "C225") (pin "2") (pinfunction "-_2") (pintype "passive"))
      (node (ref "C264") (pin "2") (pinfunction "-_2") (pintype "passive"))
      (node (ref "C303") (pin "2") (pinfunction "-_2") (pintype "passive"))
      (node (ref "C342") (pin "2") (pinfunction "-_2") (pintype "passive"))
      (node (ref "C381") (pin "2") (pinfunction "-_2") (pintype "passive"))
      (node (ref "C420") (pin "2") (pinfunction "-_2") (pintype "passive"))
      (node (ref "C459") (pin "2") (pinfunction "-_2") (pintype "passive"))
      (node (ref "C498") (pin "2") (pinfunction "-_2") (pintype "passive"))
      (node (ref "P9") (pin "5") (pinfunction "5_5") (pintype "passive"))
    )
    (net (code "31") (name "/CS31") (class "Default")
      (node (ref "C187") (pin "2") (pinfunction "-_2") (pintype "passive"))
      (node (ref "C226") (pin "2") (pinfunction "-_2") (pintype "passive"))
      (node (ref "C265") (pin "2") (pinfunction "-_2") (pintype "passive"))
      (node (ref "C304") (pin "2") (pinfunction "-_2") (pintype "passive"))
      (node (ref "C343") (pin "2") (pinfunction "-_2") (pintype "passive"))
      (node (ref "C382") (pin "2") (pinfunction "-_2") (pintype "passive"))
      (node (ref "C421") (pin "2") (pinfunction "-_2") (pintype "passive"))
      (node (ref "C460") (pin "2") (pinfunction "-_2") (pintype "passive"))
      (node (ref "C499") (pin "2") (pinfunction "-_2") (pintype "passive"))
      (node (ref "P9") (pin "6") (pinfunction "6_6") (pintype "passive"))
    )
    (net (code "32") (name "/CS32") (class "Default")
      (node (ref "C188") (pin "2") (pinfunction "-_2") (pintype "passive"))
      (node (ref "C227") (pin "2") (pinfunction "-_2") (pintype "passive"))
      (node (ref "C266") (pin "2") (pinfunction "-_2") (pintype "passive"))
      (node (ref "C305") (pin "2") (pinfunction "-_2") (pintype "passive"))
      (node (ref "C344") (pin "2") (pinfunction "-_2") (pintype "passive"))
      (node (ref "C383") (pin "2") (pinfunction "-_2") (pintype "passive"))
      (node (ref "C422") (pin "2") (pinfunction "-_2") (pintype "passive"))
      (node (ref "C461") (pin "2") (pinfunction "-_2") (pintype "passive"))
      (node (ref "C500") (pin "2") (pinfunction "-_2") (pintype "passive"))
      (node (ref "P9") (pin "7") (pinfunction "7_7") (pintype "passive"))
    )
    (net (code "33") (name "/CS33") (class "Default")
      (node (ref "C189") (pin "2") (pinfunction "-_2") (pintype "passive"))
      (node (ref "C228") (pin "2") (pinfunction "-_2") (pintype "passive"))
      (node (ref "C267") (pin "2") (pinfunction "-_2") (pintype "passive"))
      (node (ref "C306") (pin "2") (pinfunction "-_2") (pintype "passive"))
      (node (ref "C345") (pin "2") (pinfunction "-_2") (pintype "passive"))
      (node (ref "C384") (pin "2") (pinfunction "-_2") (pintype "passive"))
      (node (ref "C423") (pin "2") (pinfunction "-_2") (pintype "passive"))
      (node (ref "C462") (pin "2") (pinfunction "-_2") (pintype "passive"))
      (node (ref "C501") (pin "2") (pinfunction "-_2") (pintype "passive"))
      (node (ref "P9") (pin "8") (pinfunction "8_8") (pintype "passive"))
    )
    (net (code "34") (name "/CS34") (class "Default")
      (node (ref "C190") (pin "2") (pinfunction "-_2") (pintype "passive"))
      (node (ref "C229") (pin "2") (pinfunction "-_2") (pintype "passive"))
      (node (ref "C268") (pin "2") (pinfunction "-_2") (pintype "passive"))
      (node (ref "C307") (pin "2") (pinfunction "-_2") (pintype "passive"))
      (node (ref "C346") (pin "2") (pinfunction "-_2") (pintype "passive"))
      (node (ref "C385") (pin "2") (pinfunction "-_2") (pintype "passive"))
      (node (ref "C424") (pin "2") (pinfunction "-_2") (pintype "passive"))
      (node (ref "C463") (pin "2") (pinfunction "-_2") (pintype "passive"))
      (node (ref "C502") (pin "2") (pinfunction "-_2") (pintype "passive"))
      (node (ref "P9") (pin "9") (pinfunction "9_9") (pintype "passive"))
    )
    (net (code "35") (name "/CS35") (class "Default")
      (node (ref "C191") (pin "2") (pinfunction "-_2") (pintype "passive"))
      (node (ref "C230") (pin "2") (pinfunction "-_2") (pintype "passive"))
      (node (ref "C269") (pin "2") (pinfunction "-_2") (pintype "passive"))
      (node (ref "C308") (pin "2") (pinfunction "-_2") (pintype "passive"))
      (node (ref "C347") (pin "2") (pinfunction "-_2") (pintype "passive"))
      (node (ref "C386") (pin "2") (pinfunction "-_2") (pintype "passive"))
      (node (ref "C425") (pin "2") (pinfunction "-_2") (pintype "passive"))
      (node (ref "C464") (pin "2") (pinfunction "-_2") (pintype "passive"))
      (node (ref "C503") (pin "2") (pinfunction "-_2") (pintype "passive"))
      (node (ref "P9") (pin "10") (pinfunction "10_10") (pintype "passive"))
    )
    (net (code "36") (name "/CS36") (class "Default")
      (node (ref "C192") (pin "2") (pinfunction "-_2") (pintype "passive"))
      (node (ref "C231") (pin "2") (pinfunction "-_2") (pintype "passive"))
      (node (ref "C270") (pin "2") (pinfunction "-_2") (pintype "passive"))
      (node (ref "C309") (pin "2") (pinfunction "-_2") (pintype "passive"))
      (node (ref "C348") (pin "2") (pinfunction "-_2") (pintype "passive"))
      (node (ref "C387") (pin "2") (pinfunction "-_2") (pintype "passive"))
      (node (ref "C426") (pin "2") (pinfunction "-_2") (pintype "passive"))
      (node (ref "C465") (pin "2") (pinfunction "-_2") (pintype "passive"))
      (node (ref "C504") (pin "2") (pinfunction "-_2") (pintype "passive"))
      (node (ref "P9") (pin "11") (pinfunction "11_11") (pintype "passive"))
    )
    (net (code "37") (name "/CS37") (class "Default")
      (node (ref "C193") (pin "2") (pinfunction "-_2") (pintype "passive"))
      (node (ref "C232") (pin "2") (pinfunction "-_2") (pintype "passive"))
      (node (ref "C271") (pin "2") (pinfunction "-_2") (pintype "passive"))
      (node (ref "C310") (pin "2") (pinfunction "-_2") (pintype "passive"))
      (node (ref "C349") (pin "2") (pinfunction "-_2") (pintype "passive"))
      (node (ref "C388") (pin "2") (pinfunction "-_2") (pintype "passive"))
      (node (ref "C427") (pin "2") (pinfunction "-_2") (pintype "passive"))
      (node (ref "C466") (pin "2") (pinfunction "-_2") (pintype "passive"))
      (node (ref "C505") (pin "2") (pinfunction "-_2") (pintype "passive"))
      (node (ref "P9") (pin "12") (pinfunction "12_12") (pintype "passive"))
    )
    (net (code "38") (name "/CS38") (class "Default")
      (node (ref "C194") (pin "2") (pinfunction "-_2") (pintype "passive"))
      (node (ref "C233") (pin "2") (pinfunction "-_2") (pintype "passive"))
      (node (ref "C272") (pin "2") (pinfunction "-_2") (pintype "passive"))
      (node (ref "C311") (pin "2") (pinfunction "-_2") (pintype "passive"))
      (node (ref "C350") (pin "2") (pinfunction "-_2") (pintype "passive"))
      (node (ref "C389") (pin "2") (pinfunction "-_2") (pintype "passive"))
      (node (ref "C428") (pin "2") (pinfunction "-_2") (pintype "passive"))
      (node (ref "C467") (pin "2") (pinfunction "-_2") (pintype "passive"))
      (node (ref "C506") (pin "2") (pinfunction "-_2") (pintype "passive"))
      (node (ref "P9") (pin "13") (pinfunction "13_13") (pintype "passive"))
    )
    (net (code "39") (name "/CS39") (class "Default")
      (node (ref "C195") (pin "2") (pinfunction "-_2") (pintype "passive"))
      (node (ref "C234") (pin "2") (pinfunction "-_2") (pintype "passive"))
      (node (ref "C273") (pin "2") (pinfunction "-_2") (pintype "passive"))
      (node (ref "C312") (pin "2") (pinfunction "-_2") (pintype "passive"))
      (node (ref "C351") (pin "2") (pinfunction "-_2") (pintype "passive"))
      (node (ref "C390") (pin "2") (pinfunction "-_2") (pintype "passive"))
      (node (ref "C429") (pin "2") (pinfunction "-_2") (pintype "passive"))
      (node (ref "C468") (pin "2") (pinfunction "-_2") (pintype "passive"))
      (node (ref "C507") (pin "2") (pinfunction "-_2") (pintype "passive"))
      (node (ref "P9") (pin "14") (pinfunction "14_14") (pintype "passive"))
    )
    (net (code "40") (name "/SW1") (class "Default")
      (node (ref "C157") (pin "1") (pinfunction "+_1") (pintype "passive"))
      (node (ref "C158") (pin "1") (pinfunction "+_1") (pintype "passive"))
      (node (ref "C159") (pin "1") (pinfunction "+_1") (pintype "passive"))
      (node (ref "C160") (pin "1") (pinfunction "+_1") (pintype "passive"))
      (node (ref "C161") (pin "1") (pinfunction "+_1") (pintype "passive"))
      (node (ref "C162") (pin "1") (pinfunction "+_1") (pintype "passive"))
      (node (ref "C163") (pin "1") (pinfunction "+_1") (pintype "passive"))
      (node (ref "C164") (pin "1") (pinfunction "+_1") (pintype "passive"))
      (node (ref "C165") (pin "1") (pinfunction "+_1") (pintype "passive"))
      (node (ref "C166") (pin "1") (pinfunction "+_1") (pintype "passive"))
      (node (ref "C167") (pin "1") (pinfunction "+_1") (pintype "passive"))
      (node (ref "C168") (pin "1") (pinfunction "+_1") (pintype "passive"))
      (node (ref "C169") (pin "1") (pinfunction "+_1") (pintype "passive"))
      (node (ref "C170") (pin "1") (pinfunction "+_1") (pintype "passive"))
      (node (ref "C171") (pin "1") (pinfunction "+_1") (pintype "passive"))
      (node (ref "C172") (pin "1") (pinfunction "+_1") (pintype "passive"))
      (node (ref "C173") (pin "1") (pinfunction "+_1") (pintype "passive"))
      (node (ref "C174") (pin "1") (pinfunction "+_1") (pintype "passive"))
      (node (ref "C175") (pin "1") (pinfunction "+_1") (pintype "passive"))
      (node (ref "C176") (pin "1") (pinfunction "+_1") (pintype "passive"))
      (node (ref "C177") (pin "1") (pinfunction "+_1") (pintype "passive"))
      (node (ref "C178") (pin "1") (pinfunction "+_1") (pintype "passive"))
      (node (ref "C179") (pin "1") (pinfunction "+_1") (pintype "passive"))
      (node (ref "C180") (pin "1") (pinfunction "+_1") (pintype "passive"))
      (node (ref "C181") (pin "1") (pinfunction "+_1") (pintype "passive"))
      (node (ref "C182") (pin "1") (pinfunction "+_1") (pintype "passive"))
      (node (ref "C183") (pin "1") (pinfunction "+_1") (pintype "passive"))
      (node (ref "C184") (pin "1") (pinfunction "+_1") (pintype "passive"))
      (node (ref "C185") (pin "1") (pinfunction "+_1") (pintype "passive"))
      (node (ref "C186") (pin "1") (pinfunction "+_1") (pintype "passive"))
      (node (ref "C187") (pin "1") (pinfunction "+_1") (pintype "passive"))
      (node (ref "C188") (pin "1") (pinfunction "+_1") (pintype "passive"))
      (node (ref "C189") (pin "1") (pinfunction "+_1") (pintype "passive"))
      (node (ref "C190") (pin "1") (pinfunction "+_1") (pintype "passive"))
      (node (ref "C191") (pin "1") (pinfunction "+_1") (pintype "passive"))
      (node (ref "C192") (pin "1") (pinfunction "+_1") (pintype "passive"))
      (node (ref "C193") (pin "1") (pinfunction "+_1") (pintype "passive"))
      (node (ref "C194") (pin "1") (pinfunction "+_1") (pintype "passive"))
      (node (ref "C195") (pin "1") (pinfunction "+_1") (pintype "passive"))
      (node (ref "P10") (pin "9") (pinfunction "9_9") (pintype "passive"))
    )
    (net (code "41") (name "/SW2") (class "Default")
      (node (ref "C196") (pin "1") (pinfunction "+_1") (pintype "passive"))
      (node (ref "C197") (pin "1") (pinfunction "+_1") (pintype "passive"))
      (node (ref "C198") (pin "1") (pinfunction "+_1") (pintype "passive"))
      (node (ref "C199") (pin "1") (pinfunction "+_1") (pintype "passive"))
      (node (ref "C200") (pin "1") (pinfunction "+_1") (pintype "passive"))
      (node (ref "C201") (pin "1") (pinfunction "+_1") (pintype "passive"))
      (node (ref "C202") (pin "1") (pinfunction "+_1") (pintype "passive"))
      (node (ref "C203") (pin "1") (pinfunction "+_1") (pintype "passive"))
      (node (ref "C204") (pin "1") (pinfunction "+_1") (pintype "passive"))
      (node (ref "C205") (pin "1") (pinfunction "+_1") (pintype "passive"))
      (node (ref "C206") (pin "1") (pinfunction "+_1") (pintype "passive"))
      (node (ref "C207") (pin "1") (pinfunction "+_1") (pintype "passive"))
      (node (ref "C208") (pin "1") (pinfunction "+_1") (pintype "passive"))
      (node (ref "C209") (pin "1") (pinfunction "+_1") (pintype "passive"))
      (node (ref "C210") (pin "1") (pinfunction "+_1") (pintype "passive"))
      (node (ref "C211") (pin "1") (pinfunction "+_1") (pintype "passive"))
      (node (ref "C212") (pin "1") (pinfunction "+_1") (pintype "passive"))
      (node (ref "C213") (pin "1") (pinfunction "+_1") (pintype "passive"))
      (node (ref "C214") (pin "1") (pinfunction "+_1") (pintype "passive"))
      (node (ref "C215") (pin "1") (pinfunction "+_1") (pintype "passive"))
      (node (ref "C216") (pin "1") (pinfunction "+_1") (pintype "passive"))
      (node (ref "C217") (pin "1") (pinfunction "+_1") (pintype "passive"))
      (node (ref "C218") (pin "1") (pinfunction "+_1") (pintype "passive"))
      (node (ref "C219") (pin "1") (pinfunction "+_1") (pintype "passive"))
      (node (ref "C220") (pin "1") (pinfunction "+_1") (pintype "passive"))
      (node (ref "C221") (pin "1") (pinfunction "+_1") (pintype "passive"))
      (node (ref "C222") (pin "1") (pinfunction "+_1") (pintype "passive"))
      (node (ref "C223") (pin "1") (pinfunction "+_1") (pintype "passive"))
      (node (ref "C224") (pin "1") (pinfunction "+_1") (pintype "passive"))
      (node (ref "C225") (pin "1") (pinfunction "+_1") (pintype "passive"))
      (node (ref "C226") (pin "1") (pinfunction "+_1") (pintype "passive"))
      (node (ref "C227") (pin "1") (pinfunction "+_1") (pintype "passive"))
      (node (ref "C228") (pin "1") (pinfunction "+_1") (pintype "passive"))
      (node (ref "C229") (pin "1") (pinfunction "+_1") (pintype "passive"))
      (node (ref "C230") (pin "1") (pinfunction "+_1") (pintype "passive"))
      (node (ref "C231") (pin "1") (pinfunction "+_1") (pintype "passive"))
      (node (ref "C232") (pin "1") (pinfunction "+_1") (pintype "passive"))
      (node (ref "C233") (pin "1") (pinfunction "+_1") (pintype "passive"))
      (node (ref "C234") (pin "1") (pinfunction "+_1") (pintype "passive"))
      (node (ref "P10") (pin "8") (pinfunction "8_8") (pintype "passive"))
    )
    (net (code "42") (name "/SW3") (class "Default")
      (node (ref "C235") (pin "1") (pinfunction "+_1") (pintype "passive"))
      (node (ref "C236") (pin "1") (pinfunction "+_1") (pintype "passive"))
      (node (ref "C237") (pin "1") (pinfunction "+_1") (pintype "passive"))
      (node (ref "C238") (pin "1") (pinfunction "+_1") (pintype "passive"))
      (node (ref "C239") (pin "1") (pinfunction "+_1") (pintype "passive"))
      (node (ref "C240") (pin "1") (pinfunction "+_1") (pintype "passive"))
      (node (ref "C241") (pin "1") (pinfunction "+_1") (pintype "passive"))
      (node (ref "C242") (pin "1") (pinfunction "+_1") (pintype "passive"))
      (node (ref "C243") (pin "1") (pinfunction "+_1") (pintype "passive"))
      (node (ref "C244") (pin "1") (pinfunction "+_1") (pintype "passive"))
      (node (ref "C245") (pin "1") (pinfunction "+_1") (pintype "passive"))
      (node (ref "C246") (pin "1") (pinfunction "+_1") (pintype "passive"))
      (node (ref "C247") (pin "1") (pinfunction "+_1") (pintype "passive"))
      (node (ref "C248") (pin "1") (pinfunction "+_1") (pintype "passive"))
      (node (ref "C249") (pin "1") (pinfunction "+_1") (pintype "passive"))
      (node (ref "C250") (pin "1") (pinfunction "+_1") (pintype "passive"))
      (node (ref "C251") (pin "1") (pinfunction "+_1") (pintype "passive"))
      (node (ref "C252") (pin "1") (pinfunction "+_1") (pintype "passive"))
      (node (ref "C253") (pin "1") (pinfunction "+_1") (pintype "passive"))
      (node (ref "C254") (pin "1") (pinfunction "+_1") (pintype "passive"))
      (node (ref "C255") (pin "1") (pinfunction "+_1") (pintype "passive"))
      (node (ref "C256") (pin "1") (pinfunction "+_1") (pintype "passive"))
      (node (ref "C257") (pin "1") (pinfunction "+_1") (pintype "passive"))
      (node (ref "C258") (pin "1") (pinfunction "+_1") (pintype "passive"))
      (node (ref "C259") (pin "1") (pinfunction "+_1") (pintype "passive"))
      (node (ref "C260") (pin "1") (pinfunction "+_1") (pintype "passive"))
      (node (ref "C261") (pin "1") (pinfunction "+_1") (pintype "passive"))
      (node (ref "C262") (pin "1") (pinfunction "+_1") (pintype "passive"))
      (node (ref "C263") (pin "1") (pinfunction "+_1") (pintype "passive"))
      (node (ref "C264") (pin "1") (pinfunction "+_1") (pintype "passive"))
      (node (ref "C265") (pin "1") (pinfunction "+_1") (pintype "passive"))
      (node (ref "C266") (pin "1") (pinfunction "+_1") (pintype "passive"))
      (node (ref "C267") (pin "1") (pinfunction "+_1") (pintype "passive"))
      (node (ref "C268") (pin "1") (pinfunction "+_1") (pintype "passive"))
      (node (ref "C269") (pin "1") (pinfunction "+_1") (pintype "passive"))
      (node (ref "C270") (pin "1") (pinfunction "+_1") (pintype "passive"))
      (node (ref "C271") (pin "1") (pinfunction "+_1") (pintype "passive"))
      (node (ref "C272") (pin "1") (pinfunction "+_1") (pintype "passive"))
      (node (ref "C273") (pin "1") (pinfunction "+_1") (pintype "passive"))
      (node (ref "P10") (pin "7") (pinfunction "7_7") (pintype "passive"))
    )
    (net (code "43") (name "/SW4") (class "Default")
      (node (ref "C274") (pin "1") (pinfunction "+_1") (pintype "passive"))
      (node (ref "C275") (pin "1") (pinfunction "+_1") (pintype "passive"))
      (node (ref "C276") (pin "1") (pinfunction "+_1") (pintype "passive"))
      (node (ref "C277") (pin "1") (pinfunction "+_1") (pintype "passive"))
      (node (ref "C278") (pin "1") (pinfunction "+_1") (pintype "passive"))
      (node (ref "C279") (pin "1") (pinfunction "+_1") (pintype "passive"))
      (node (ref "C280") (pin "1") (pinfunction "+_1") (pintype "passive"))
      (node (ref "C281") (pin "1") (pinfunction "+_1") (pintype "passive"))
      (node (ref "C282") (pin "1") (pinfunction "+_1") (pintype "passive"))
      (node (ref "C283") (pin "1") (pinfunction "+_1") (pintype "passive"))
      (node (ref "C284") (pin "1") (pinfunction "+_1") (pintype "passive"))
      (node (ref "C285") (pin "1") (pinfunction "+_1") (pintype "passive"))
      (node (ref "C286") (pin "1") (pinfunction "+_1") (pintype "passive"))
      (node (ref "C287") (pin "1") (pinfunction "+_1") (pintype "passive"))
      (node (ref "C288") (pin "1") (pinfunction "+_1") (pintype "passive"))
      (node (ref "C289") (pin "1") (pinfunction "+_1") (pintype "passive"))
      (node (ref "C290") (pin "1") (pinfunction "+_1") (pintype "passive"))
      (node (ref "C291") (pin "1") (pinfunction "+_1") (pintype "passive"))
      (node (ref "C292") (pin "1") (pinfunction "+_1") (pintype "passive"))
      (node (ref "C293") (pin "1") (pinfunction "+_1") (pintype "passive"))
      (node (ref "C294") (pin "1") (pinfunction "+_1") (pintype "passive"))
      (node (ref "C295") (pin "1") (pinfunction "+_1") (pintype "passive"))
      (node (ref "C296") (pin "1") (pinfunction "+_1") (pintype "passive"))
      (node (ref "C297") (pin "1") (pinfunction "+_1") (pintype "passive"))
      (node (ref "C298") (pin "1") (pinfunction "+_1") (pintype "passive"))
      (node (ref "C299") (pin "1") (pinfunction "+_1") (pintype "passive"))
      (node (ref "C300") (pin "1") (pinfunction "+_1") (pintype "passive"))
      (node (ref "C301") (pin "1") (pinfunction "+_1") (pintype "passive"))
      (node (ref "C302") (pin "1") (pinfunction "+_1") (pintype "passive"))
      (node (ref "C303") (pin "1") (pinfunction "+_1") (pintype "passive"))
      (node (ref "C304") (pin "1") (pinfunction "+_1") (pintype "passive"))
      (node (ref "C305") (pin "1") (pinfunction "+_1") (pintype "passive"))
      (node (ref "C306") (pin "1") (pinfunction "+_1") (pintype "passive"))
      (node (ref "C307") (pin "1") (pinfunction "+_1") (pintype "passive"))
      (node (ref "C308") (pin "1") (pinfunction "+_1") (pintype "passive"))
      (node (ref "C309") (pin "1") (pinfunction "+_1") (pintype "passive"))
      (node (ref "C310") (pin "1") (pinfunction "+_1") (pintype "passive"))
      (node (ref "C311") (pin "1") (pinfunction "+_1") (pintype "passive"))
      (node (ref "C312") (pin "1") (pinfunction "+_1") (pintype "passive"))
      (node (ref "P10") (pin "6") (pinfunction "6_6") (pintype "passive"))
    )
    (net (code "44") (name "/SW5") (class "Default")
      (node (ref "C313") (pin "1") (pinfunction "+_1") (pintype "passive"))
      (node (ref "C314") (pin "1") (pinfunction "+_1") (pintype "passive"))
      (node (ref "C315") (pin "1") (pinfunction "+_1") (pintype "passive"))
      (node (ref "C316") (pin "1") (pinfunction "+_1") (pintype "passive"))
      (node (ref "C317") (pin "1") (pinfunction "+_1") (pintype "passive"))
      (node (ref "C318") (pin "1") (pinfunction "+_1") (pintype "passive"))
      (node (ref "C319") (pin "1") (pinfunction "+_1") (pintype "passive"))
      (node (ref "C320") (pin "1") (pinfunction "+_1") (pintype "passive"))
      (node (ref "C321") (pin "1") (pinfunction "+_1") (pintype "passive"))
      (node (ref "C322") (pin "1") (pinfunction "+_1") (pintype "passive"))
      (node (ref "C323") (pin "1") (pinfunction "+_1") (pintype "passive"))
      (node (ref "C324") (pin "1") (pinfunction "+_1") (pintype "passive"))
      (node (ref "C325") (pin "1") (pinfunction "+_1") (pintype "passive"))
      (node (ref "C326") (pin "1") (pinfunction "+_1") (pintype "passive"))
      (node (ref "C327") (pin "1") (pinfunction "+_1") (pintype "passive"))
      (node (ref "C328") (pin "1") (pinfunction "+_1") (pintype "passive"))
      (node (ref "C329") (pin "1") (pinfunction "+_1") (pintype "passive"))
      (node (ref "C330") (pin "1") (pinfunction "+_1") (pintype "passive"))
      (node (ref "C331") (pin "1") (pinfunction "+_1") (pintype "passive"))
      (node (ref "C332") (pin "1") (pinfunction "+_1") (pintype "passive"))
      (node (ref "C333") (pin "1") (pinfunction "+_1") (pintype "passive"))
      (node (ref "C334") (pin "1") (pinfunction "+_1") (pintype "passive"))
      (node (ref "C335") (pin "1") (pinfunction "+_1") (pintype "passive"))
      (node (ref "C336") (pin "1") (pinfunction "+_1") (pintype "passive"))
      (node (ref "C337") (pin "1") (pinfunction "+_1") (pintype "passive"))
      (node (ref "C338") (pin "1") (pinfunction "+_1") (pintype "passive"))
      (node (ref "C339") (pin "1") (pinfunction "+_1") (pintype "passive"))
      (node (ref "C340") (pin "1") (pinfunction "+_1") (pintype "passive"))
      (node (ref "C341") (pin "1") (pinfunction "+_1") (pintype "passive"))
      (node (ref "C342") (pin "1") (pinfunction "+_1") (pintype "passive"))
      (node (ref "C343") (pin "1") (pinfunction "+_1") (pintype "passive"))
      (node (ref "C344") (pin "1") (pinfunction "+_1") (pintype "passive"))
      (node (ref "C345") (pin "1") (pinfunction "+_1") (pintype "passive"))
      (node (ref "C346") (pin "1") (pinfunction "+_1") (pintype "passive"))
      (node (ref "C347") (pin "1") (pinfunction "+_1") (pintype "passive"))
      (node (ref "C348") (pin "1") (pinfunction "+_1") (pintype "passive"))
      (node (ref "C349") (pin "1") (pinfunction "+_1") (pintype "passive"))
      (node (ref "C350") (pin "1") (pinfunction "+_1") (pintype "passive"))
      (node (ref "C351") (pin "1") (pinfunction "+_1") (pintype "passive"))
      (node (ref "P10") (pin "5") (pinfunction "5_5") (pintype "passive"))
    )
    (net (code "45") (name "/SW6") (class "Default")
      (node (ref "C352") (pin "1") (pinfunction "+_1") (pintype "passive"))
      (node (ref "C353") (pin "1") (pinfunction "+_1") (pintype "passive"))
      (node (ref "C354") (pin "1") (pinfunction "+_1") (pintype "passive"))
      (node (ref "C355") (pin "1") (pinfunction "+_1") (pintype "passive"))
      (node (ref "C356") (pin "1") (pinfunction "+_1") (pintype "passive"))
      (node (ref "C357") (pin "1") (pinfunction "+_1") (pintype "passive"))
      (node (ref "C358") (pin "1") (pinfunction "+_1") (pintype "passive"))
      (node (ref "C359") (pin "1") (pinfunction "+_1") (pintype "passive"))
      (node (ref "C360") (pin "1") (pinfunction "+_1") (pintype "passive"))
      (node (ref "C361") (pin "1") (pinfunction "+_1") (pintype "passive"))
      (node (ref "C362") (pin "1") (pinfunction "+_1") (pintype "passive"))
      (node (ref "C363") (pin "1") (pinfunction "+_1") (pintype "passive"))
      (node (ref "C364") (pin "1") (pinfunction "+_1") (pintype "passive"))
      (node (ref "C365") (pin "1") (pinfunction "+_1") (pintype "passive"))
      (node (ref "C366") (pin "1") (pinfunction "+_1") (pintype "passive"))
      (node (ref "C367") (pin "1") (pinfunction "+_1") (pintype "passive"))
      (node (ref "C368") (pin "1") (pinfunction "+_1") (pintype "passive"))
      (node (ref "C369") (pin "1") (pinfunction "+_1") (pintype "passive"))
      (node (ref "C370") (pin "1") (pinfunction "+_1") (pintype "passive"))
      (node (ref "C371") (pin "1") (pinfunction "+_1") (pintype "passive"))
      (node (ref "C372") (pin "1") (pinfunction "+_1") (pintype "passive"))
      (node (ref "C373") (pin "1") (pinfunction "+_1") (pintype "passive"))
      (node (ref "C374") (pin "1") (pinfunction "+_1") (pintype "passive"))
      (node (ref "C375") (pin "1") (pinfunction "+_1") (pintype "passive"))
      (node (ref "C376") (pin "1") (pinfunction "+_1") (pintype "passive"))
      (node (ref "C377") (pin "1") (pinfunction "+_1") (pintype "passive"))
      (node (ref "C378") (pin "1") (pinfunction "+_1") (pintype "passive"))
      (node (ref "C379") (pin "1") (pinfunction "+_1") (pintype "passive"))
      (node (ref "C380") (pin "1") (pinfunction "+_1") (pintype "passive"))
      (node (ref "C381") (pin "1") (pinfunction "+_1") (pintype "passive"))
      (node (ref "C382") (pin "1") (pinfunction "+_1") (pintype "passive"))
      (node (ref "C383") (pin "1") (pinfunction "+_1") (pintype "passive"))
      (node (ref "C384") (pin "1") (pinfunction "+_1") (pintype "passive"))
      (node (ref "C385") (pin "1") (pinfunction "+_1") (pintype "passive"))
      (node (ref "C386") (pin "1") (pinfunction "+_1") (pintype "passive"))
      (node (ref "C387") (pin "1") (pinfunction "+_1") (pintype "passive"))
      (node (ref "C388") (pin "1") (pinfunction "+_1") (pintype "passive"))
      (node (ref "C389") (pin "1") (pinfunction "+_1") (pintype "passive"))
      (node (ref "C390") (pin "1") (pinfunction "+_1") (pintype "passive"))
      (node (ref "P10") (pin "4") (pinfunction "4_4") (pintype "passive"))
    )
    (net (code "46") (name "/SW7") (class "Default")
      (node (ref "C391") (pin "1") (pinfunction "+_1") (pintype "passive"))
      (node (ref "C392") (pin "1") (pinfunction "+_1") (pintype "passive"))
      (node (ref "C393") (pin "1") (pinfunction "+_1") (pintype "passive"))
      (node (ref "C394") (pin "1") (pinfunction "+_1") (pintype "passive"))
      (node (ref "C395") (pin "1") (pinfunction "+_1") (pintype "passive"))
      (node (ref "C396") (pin "1") (pinfunction "+_1") (pintype "passive"))
      (node (ref "C397") (pin "1") (pinfunction "+_1") (pintype "passive"))
      (node (ref "C398") (pin "1") (pinfunction "+_1") (pintype "passive"))
      (node (ref "C399") (pin "1") (pinfunction "+_1") (pintype "passive"))
      (node (ref "C400") (pin "1") (pinfunction "+_1") (pintype "passive"))
      (node (ref "C401") (pin "1") (pinfunction "+_1") (pintype "passive"))
      (node (ref "C402") (pin "1") (pinfunction "+_1") (pintype "passive"))
      (node (ref "C403") (pin "1") (pinfunction "+_1") (pintype "passive"))
      (node (ref "C404") (pin "1") (pinfunction "+_1") (pintype "passive"))
      (node (ref "C405") (pin "1") (pinfunction "+_1") (pintype "passive"))
      (node (ref "C406") (pin "1") (pinfunction "+_1") (pintype "passive"))
      (node (ref "C407") (pin "1") (pinfunction "+_1") (pintype "passive"))
      (node (ref "C408") (pin "1") (pinfunction "+_1") (pintype "passive"))
      (node (ref "C409") (pin "1") (pinfunction "+_1") (pintype "passive"))
      (node (ref "C410") (pin "1") (pinfunction "+_1") (pintype "passive"))
      (node (ref "C411") (pin "1") (pinfunction "+_1") (pintype "passive"))
      (node (ref "C412") (pin "1") (pinfunction "+_1") (pintype "passive"))
      (node (ref "C413") (pin "1") (pinfunction "+_1") (pintype "passive"))
      (node (ref "C414") (pin "1") (pinfunction "+_1") (pintype "passive"))
      (node (ref "C415") (pin "1") (pinfunction "+_1") (pintype "passive"))
      (node (ref "C416") (pin "1") (pinfunction "+_1") (pintype "passive"))
      (node (ref "C417") (pin "1") (pinfunction "+_1") (pintype "passive"))
      (node (ref "C418") (pin "1") (pinfunction "+_1") (pintype "passive"))
      (node (ref "C419") (pin "1") (pinfunction "+_1") (pintype "passive"))
      (node (ref "C420") (pin "1") (pinfunction "+_1") (pintype "passive"))
      (node (ref "C421") (pin "1") (pinfunction "+_1") (pintype "passive"))
      (node (ref "C422") (pin "1") (pinfunction "+_1") (pintype "passive"))
      (node (ref "C423") (pin "1") (pinfunction "+_1") (pintype "passive"))
      (node (ref "C424") (pin "1") (pinfunction "+_1") (pintype "passive"))
      (node (ref "C425") (pin "1") (pinfunction "+_1") (pintype "passive"))
      (node (ref "C426") (pin "1") (pinfunction "+_1") (pintype "passive"))
      (node (ref "C427") (pin "1") (pinfunction "+_1") (pintype "passive"))
      (node (ref "C428") (pin "1") (pinfunction "+_1") (pintype "passive"))
      (node (ref "C429") (pin "1") (pinfunction "+_1") (pintype "passive"))
      (node (ref "P10") (pin "3") (pinfunction "3_3") (pintype "passive"))
    )
    (net (code "47") (name "/SW8") (class "Default")
      (node (ref "C430") (pin "1") (pinfunction "+_1") (pintype "passive"))
      (node (ref "C431") (pin "1") (pinfunction "+_1") (pintype "passive"))
      (node (ref "C432") (pin "1") (pinfunction "+_1") (pintype "passive"))
      (node (ref "C433") (pin "1") (pinfunction "+_1") (pintype "passive"))
      (node (ref "C434") (pin "1") (pinfunction "+_1") (pintype "passive"))
      (node (ref "C435") (pin "1") (pinfunction "+_1") (pintype "passive"))
      (node (ref "C436") (pin "1") (pinfunction "+_1") (pintype "passive"))
      (node (ref "C437") (pin "1") (pinfunction "+_1") (pintype "passive"))
      (node (ref "C438") (pin "1") (pinfunction "+_1") (pintype "passive"))
      (node (ref "C439") (pin "1") (pinfunction "+_1") (pintype "passive"))
      (node (ref "C440") (pin "1") (pinfunction "+_1") (pintype "passive"))
      (node (ref "C441") (pin "1") (pinfunction "+_1") (pintype "passive"))
      (node (ref "C442") (pin "1") (pinfunction "+_1") (pintype "passive"))
      (node (ref "C443") (pin "1") (pinfunction "+_1") (pintype "passive"))
      (node (ref "C444") (pin "1") (pinfunction "+_1") (pintype "passive"))
      (node (ref "C445") (pin "1") (pinfunction "+_1") (pintype "passive"))
      (node (ref "C446") (pin "1") (pinfunction "+_1") (pintype "passive"))
      (node (ref "C447") (pin "1") (pinfunction "+_1") (pintype "passive"))
      (node (ref "C448") (pin "1") (pinfunction "+_1") (pintype "passive"))
      (node (ref "C449") (pin "1") (pinfunction "+_1") (pintype "passive"))
      (node (ref "C450") (pin "1") (pinfunction "+_1") (pintype "passive"))
      (node (ref "C451") (pin "1") (pinfunction "+_1") (pintype "passive"))
      (node (ref "C452") (pin "1") (pinfunction "+_1") (pintype "passive"))
      (node (ref "C453") (pin "1") (pinfunction "+_1") (pintype "passive"))
      (node (ref "C454") (pin "1") (pinfunction "+_1") (pintype "passive"))
      (node (ref "C455") (pin "1") (pinfunction "+_1") (pintype "passive"))
      (node (ref "C456") (pin "1") (pinfunction "+_1") (pintype "passive"))
      (node (ref "C457") (pin "1") (pinfunction "+_1") (pintype "passive"))
      (node (ref "C458") (pin "1") (pinfunction "+_1") (pintype "passive"))
      (node (ref "C459") (pin "1") (pinfunction "+_1") (pintype "passive"))
      (node (ref "C460") (pin "1") (pinfunction "+_1") (pintype "passive"))
      (node (ref "C461") (pin "1") (pinfunction "+_1") (pintype "passive"))
      (node (ref "C462") (pin "1") (pinfunction "+_1") (pintype "passive"))
      (node (ref "C463") (pin "1") (pinfunction "+_1") (pintype "passive"))
      (node (ref "C464") (pin "1") (pinfunction "+_1") (pintype "passive"))
      (node (ref "C465") (pin "1") (pinfunction "+_1") (pintype "passive"))
      (node (ref "C466") (pin "1") (pinfunction "+_1") (pintype "passive"))
      (node (ref "C467") (pin "1") (pinfunction "+_1") (pintype "passive"))
      (node (ref "C468") (pin "1") (pinfunction "+_1") (pintype "passive"))
      (node (ref "P10") (pin "2") (pinfunction "2_2") (pintype "passive"))
    )
    (net (code "48") (name "/SW9") (class "Default")
      (node (ref "C469") (pin "1") (pinfunction "+_1") (pintype "passive"))
      (node (ref "C470") (pin "1") (pinfunction "+_1") (pintype "passive"))
      (node (ref "C471") (pin "1") (pinfunction "+_1") (pintype "passive"))
      (node (ref "C472") (pin "1") (pinfunction "+_1") (pintype "passive"))
      (node (ref "C473") (pin "1") (pinfunction "+_1") (pintype "passive"))
      (node (ref "C474") (pin "1") (pinfunction "+_1") (pintype "passive"))
      (node (ref "C475") (pin "1") (pinfunction "+_1") (pintype "passive"))
      (node (ref "C476") (pin "1") (pinfunction "+_1") (pintype "passive"))
      (node (ref "C477") (pin "1") (pinfunction "+_1") (pintype "passive"))
      (node (ref "C478") (pin "1") (pinfunction "+_1") (pintype "passive"))
      (node (ref "C479") (pin "1") (pinfunction "+_1") (pintype "passive"))
      (node (ref "C480") (pin "1") (pinfunction "+_1") (pintype "passive"))
      (node (ref "C481") (pin "1") (pinfunction "+_1") (pintype "passive"))
      (node (ref "C482") (pin "1") (pinfunction "+_1") (pintype "passive"))
      (node (ref "C483") (pin "1") (pinfunction "+_1") (pintype "passive"))
      (node (ref "C484") (pin "1") (pinfunction "+_1") (pintype "passive"))
      (node (ref "C485") (pin "1") (pinfunction "+_1") (pintype "passive"))
      (node (ref "C486") (pin "1") (pinfunction "+_1") (pintype "passive"))
      (node (ref "C487") (pin "1") (pinfunction "+_1") (pintype "passive"))
      (node (ref "C488") (pin "1") (pinfunction "+_1") (pintype "passive"))
      (node (ref "C489") (pin "1") (pinfunction "+_1") (pintype "passive"))
      (node (ref "C490") (pin "1") (pinfunction "+_1") (pintype "passive"))
      (node (ref "C491") (pin "1") (pinfunction "+_1") (pintype "passive"))
      (node (ref "C492") (pin "1") (pinfunction "+_1") (pintype "passive"))
      (node (ref "C493") (pin "1") (pinfunction "+_1") (pintype "passive"))
      (node (ref "C494") (pin "1") (pinfunction "+_1") (pintype "passive"))
      (node (ref "C495") (pin "1") (pinfunction "+_1") (pintype "passive"))
      (node (ref "C496") (pin "1") (pinfunction "+_1") (pintype "passive"))
      (node (ref "C497") (pin "1") (pinfunction "+_1") (pintype "passive"))
      (node (ref "C498") (pin "1") (pinfunction "+_1") (pintype "passive"))
      (node (ref "C499") (pin "1") (pinfunction "+_1") (pintype "passive"))
      (node (ref "C500") (pin "1") (pinfunction "+_1") (pintype "passive"))
      (node (ref "C501") (pin "1") (pinfunction "+_1") (pintype "passive"))
      (node (ref "C502") (pin "1") (pinfunction "+_1") (pintype "passive"))
      (node (ref "C503") (pin "1") (pinfunction "+_1") (pintype "passive"))
      (node (ref "C504") (pin "1") (pinfunction "+_1") (pintype "passive"))
      (node (ref "C505") (pin "1") (pinfunction "+_1") (pintype "passive"))
      (node (ref "C506") (pin "1") (pinfunction "+_1") (pintype "passive"))
      (node (ref "C507") (pin "1") (pinfunction "+_1") (pintype "passive"))
      (node (ref "P10") (pin "1") (pinfunction "1_1") (pintype "passive"))
    )
  )
)
